# EK-TM4C129EXL_REV_A.net
KiCad netlist of a schematic drawn in EAGLE
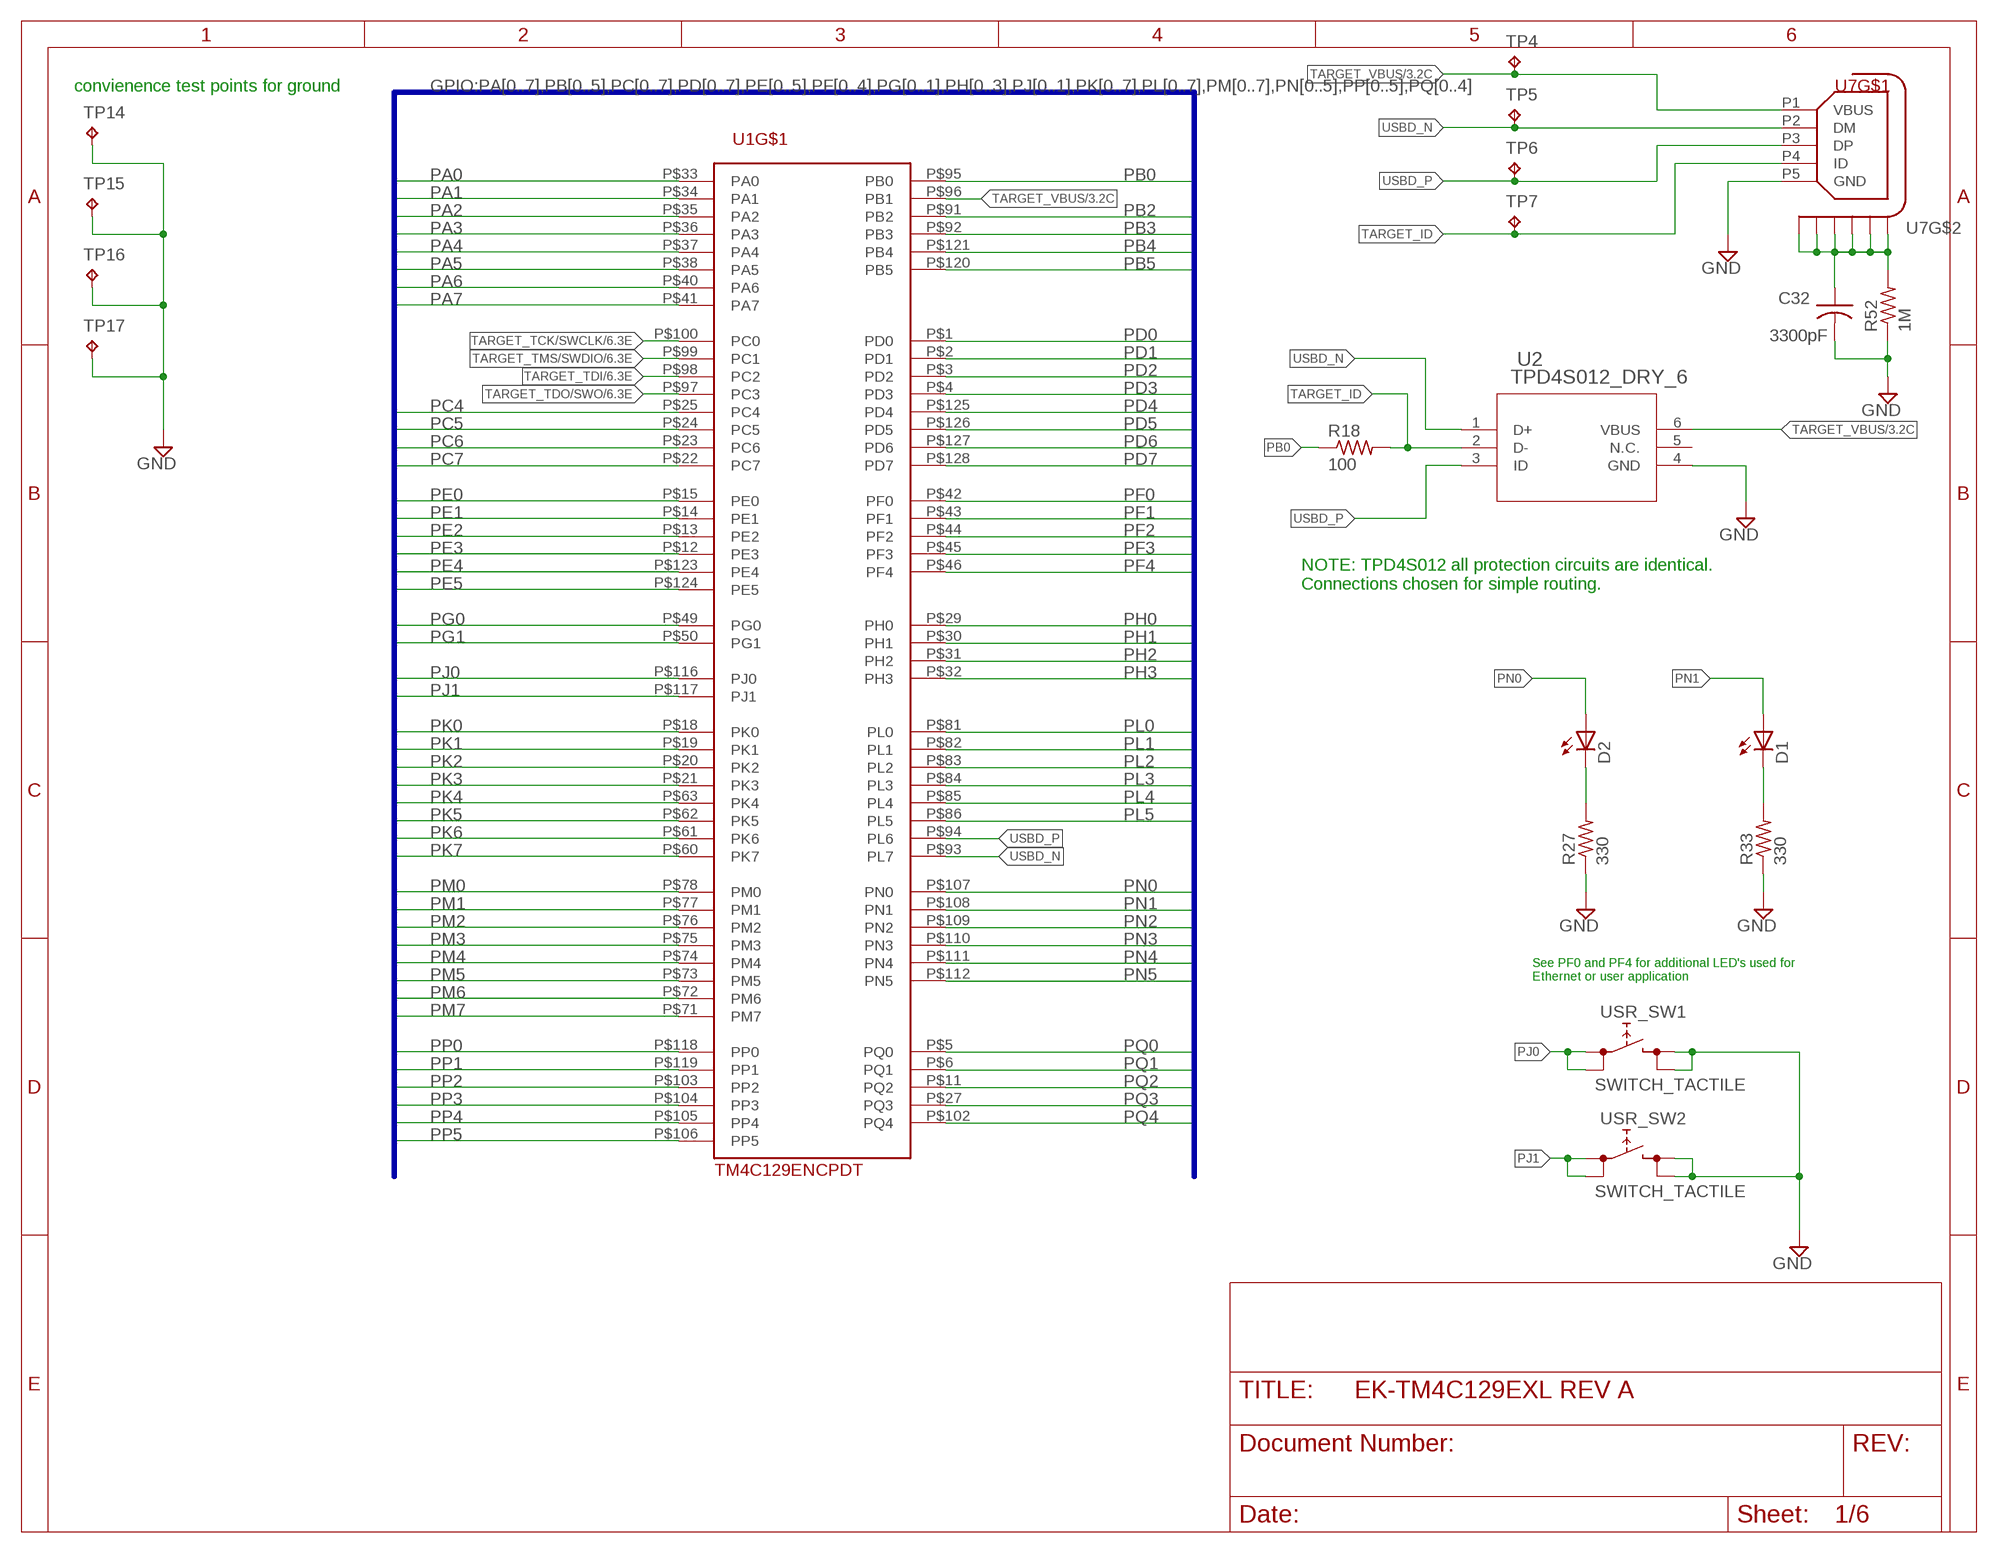
[diagram p0: schematic, sheet 1]
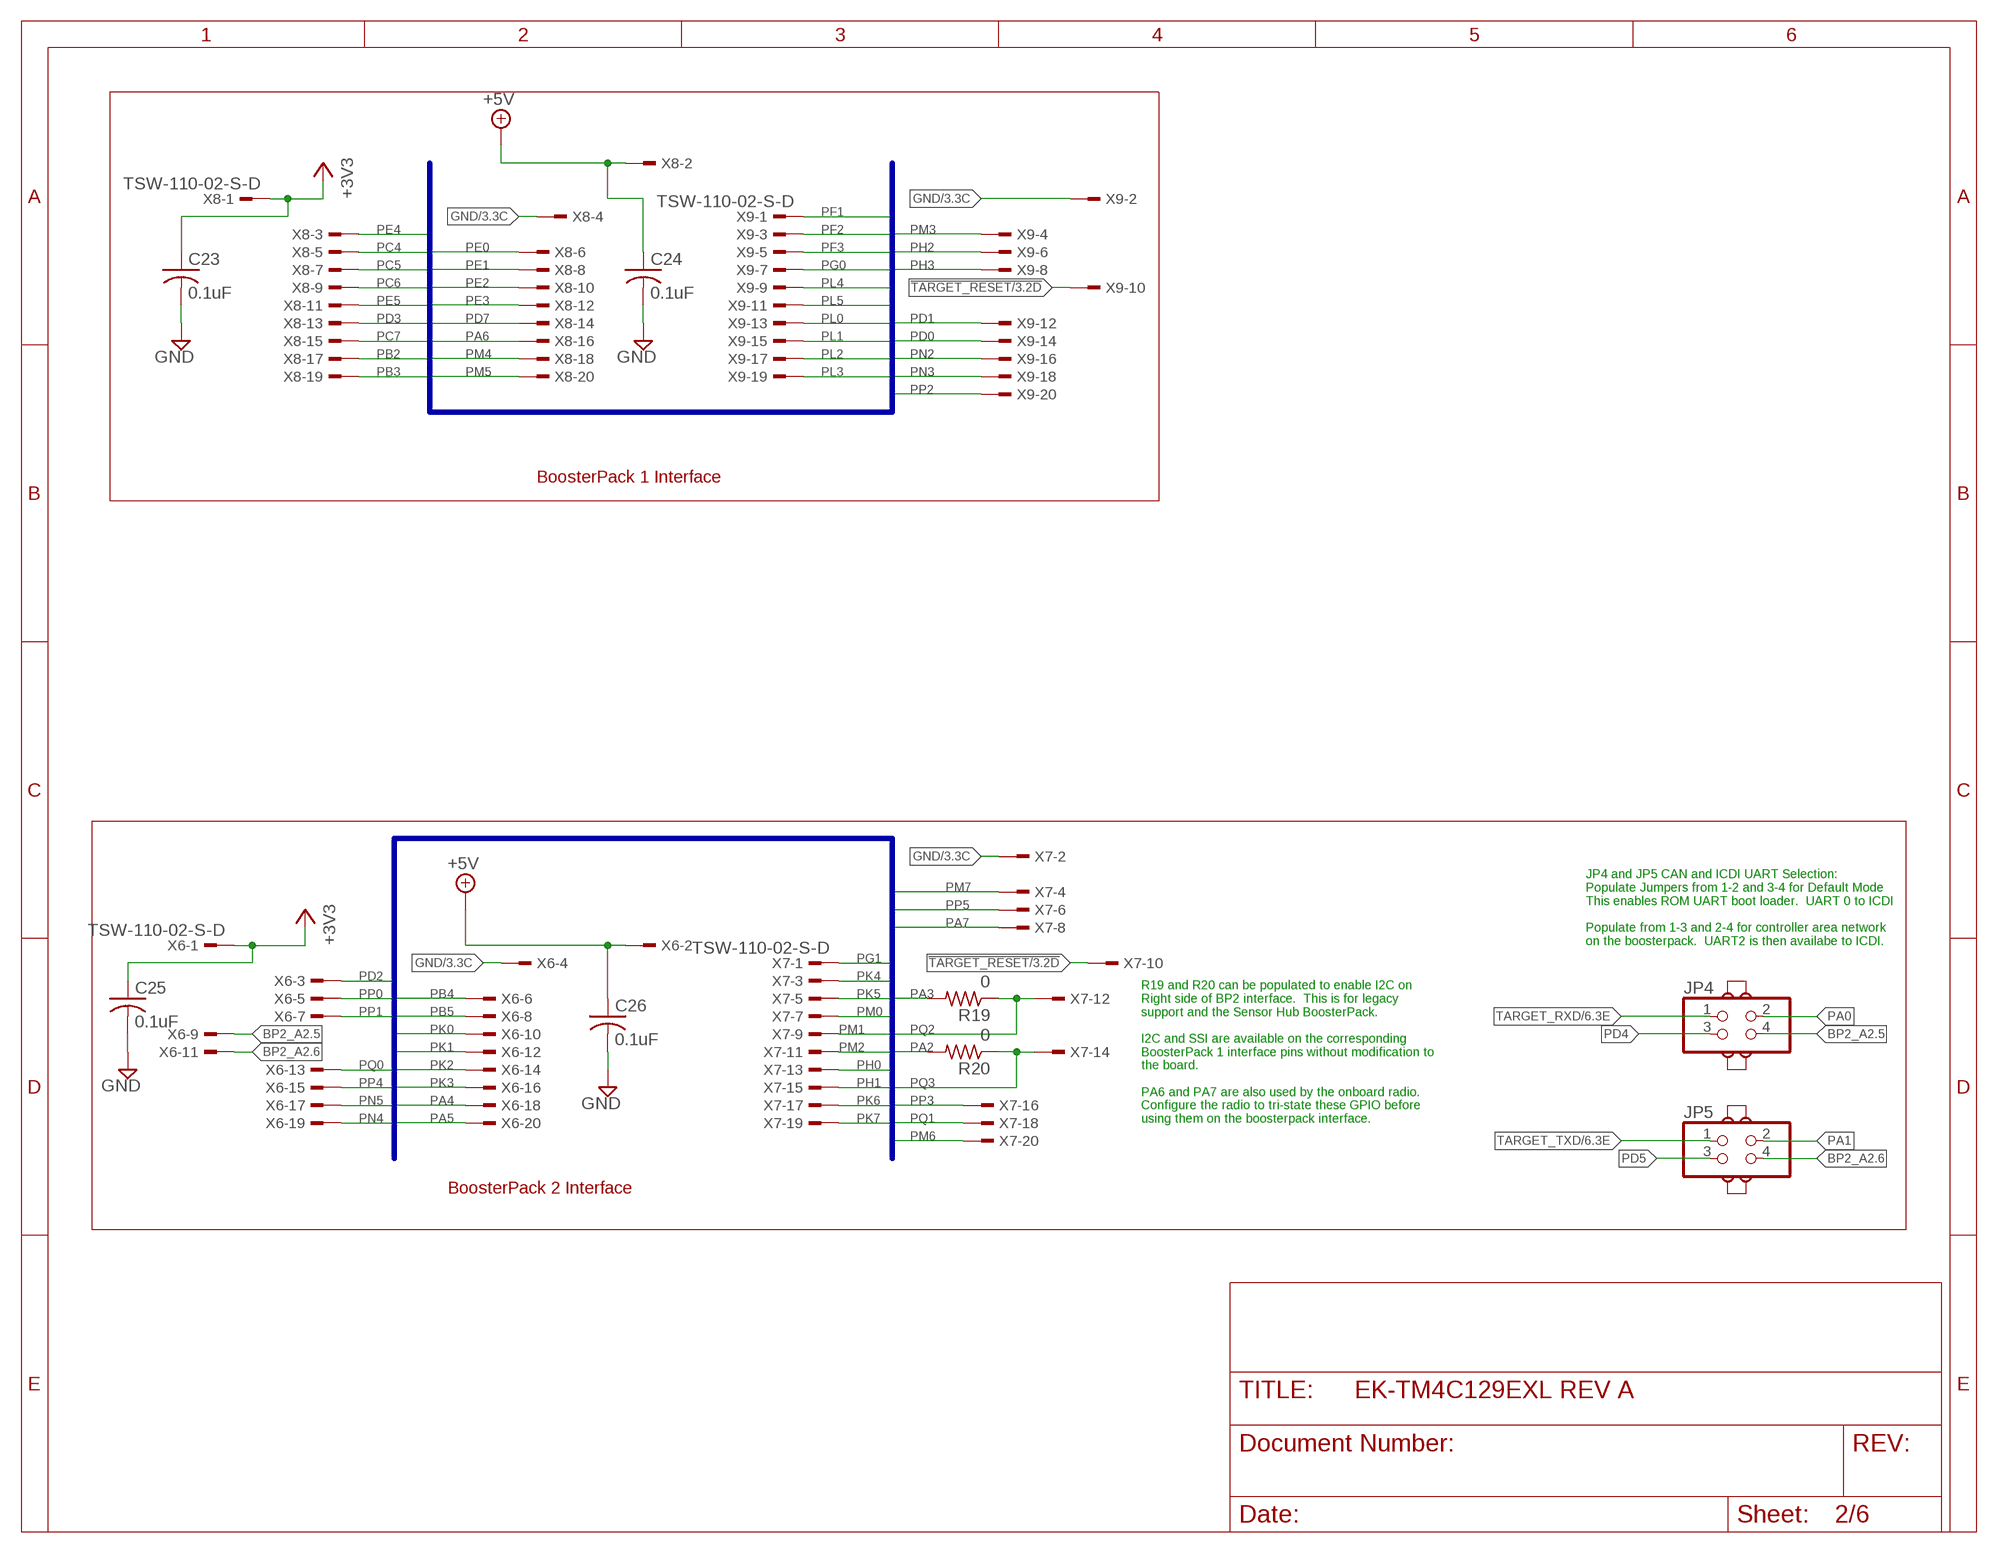
[diagram p1: schematic, sheet 2]
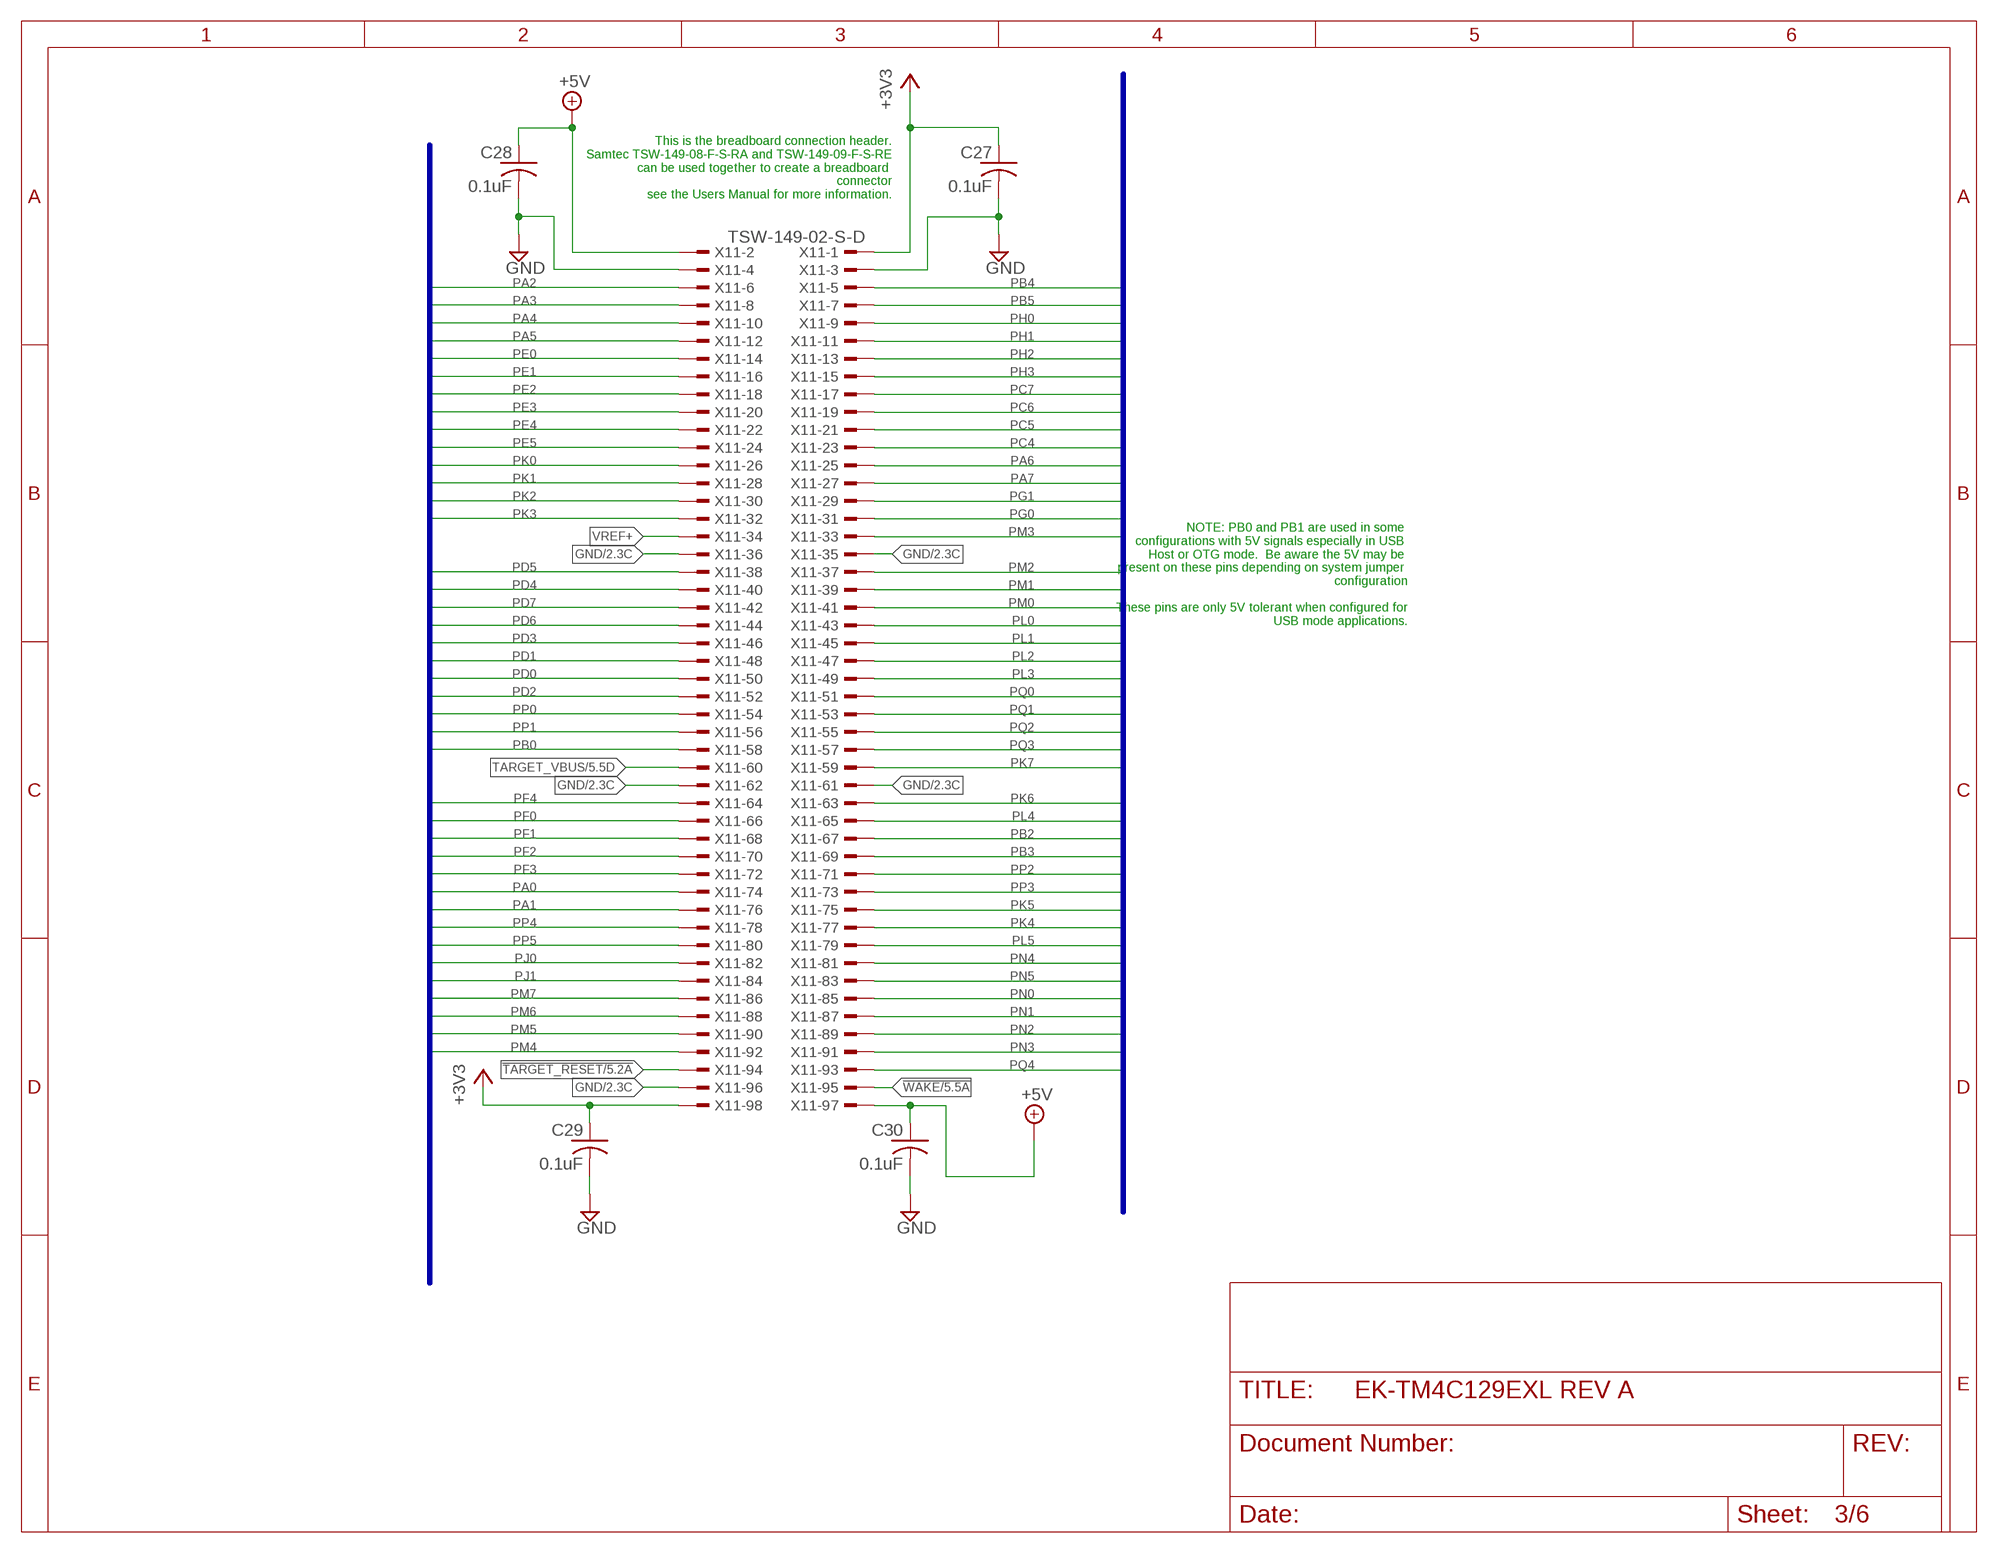
[diagram p2: schematic, sheet 3]
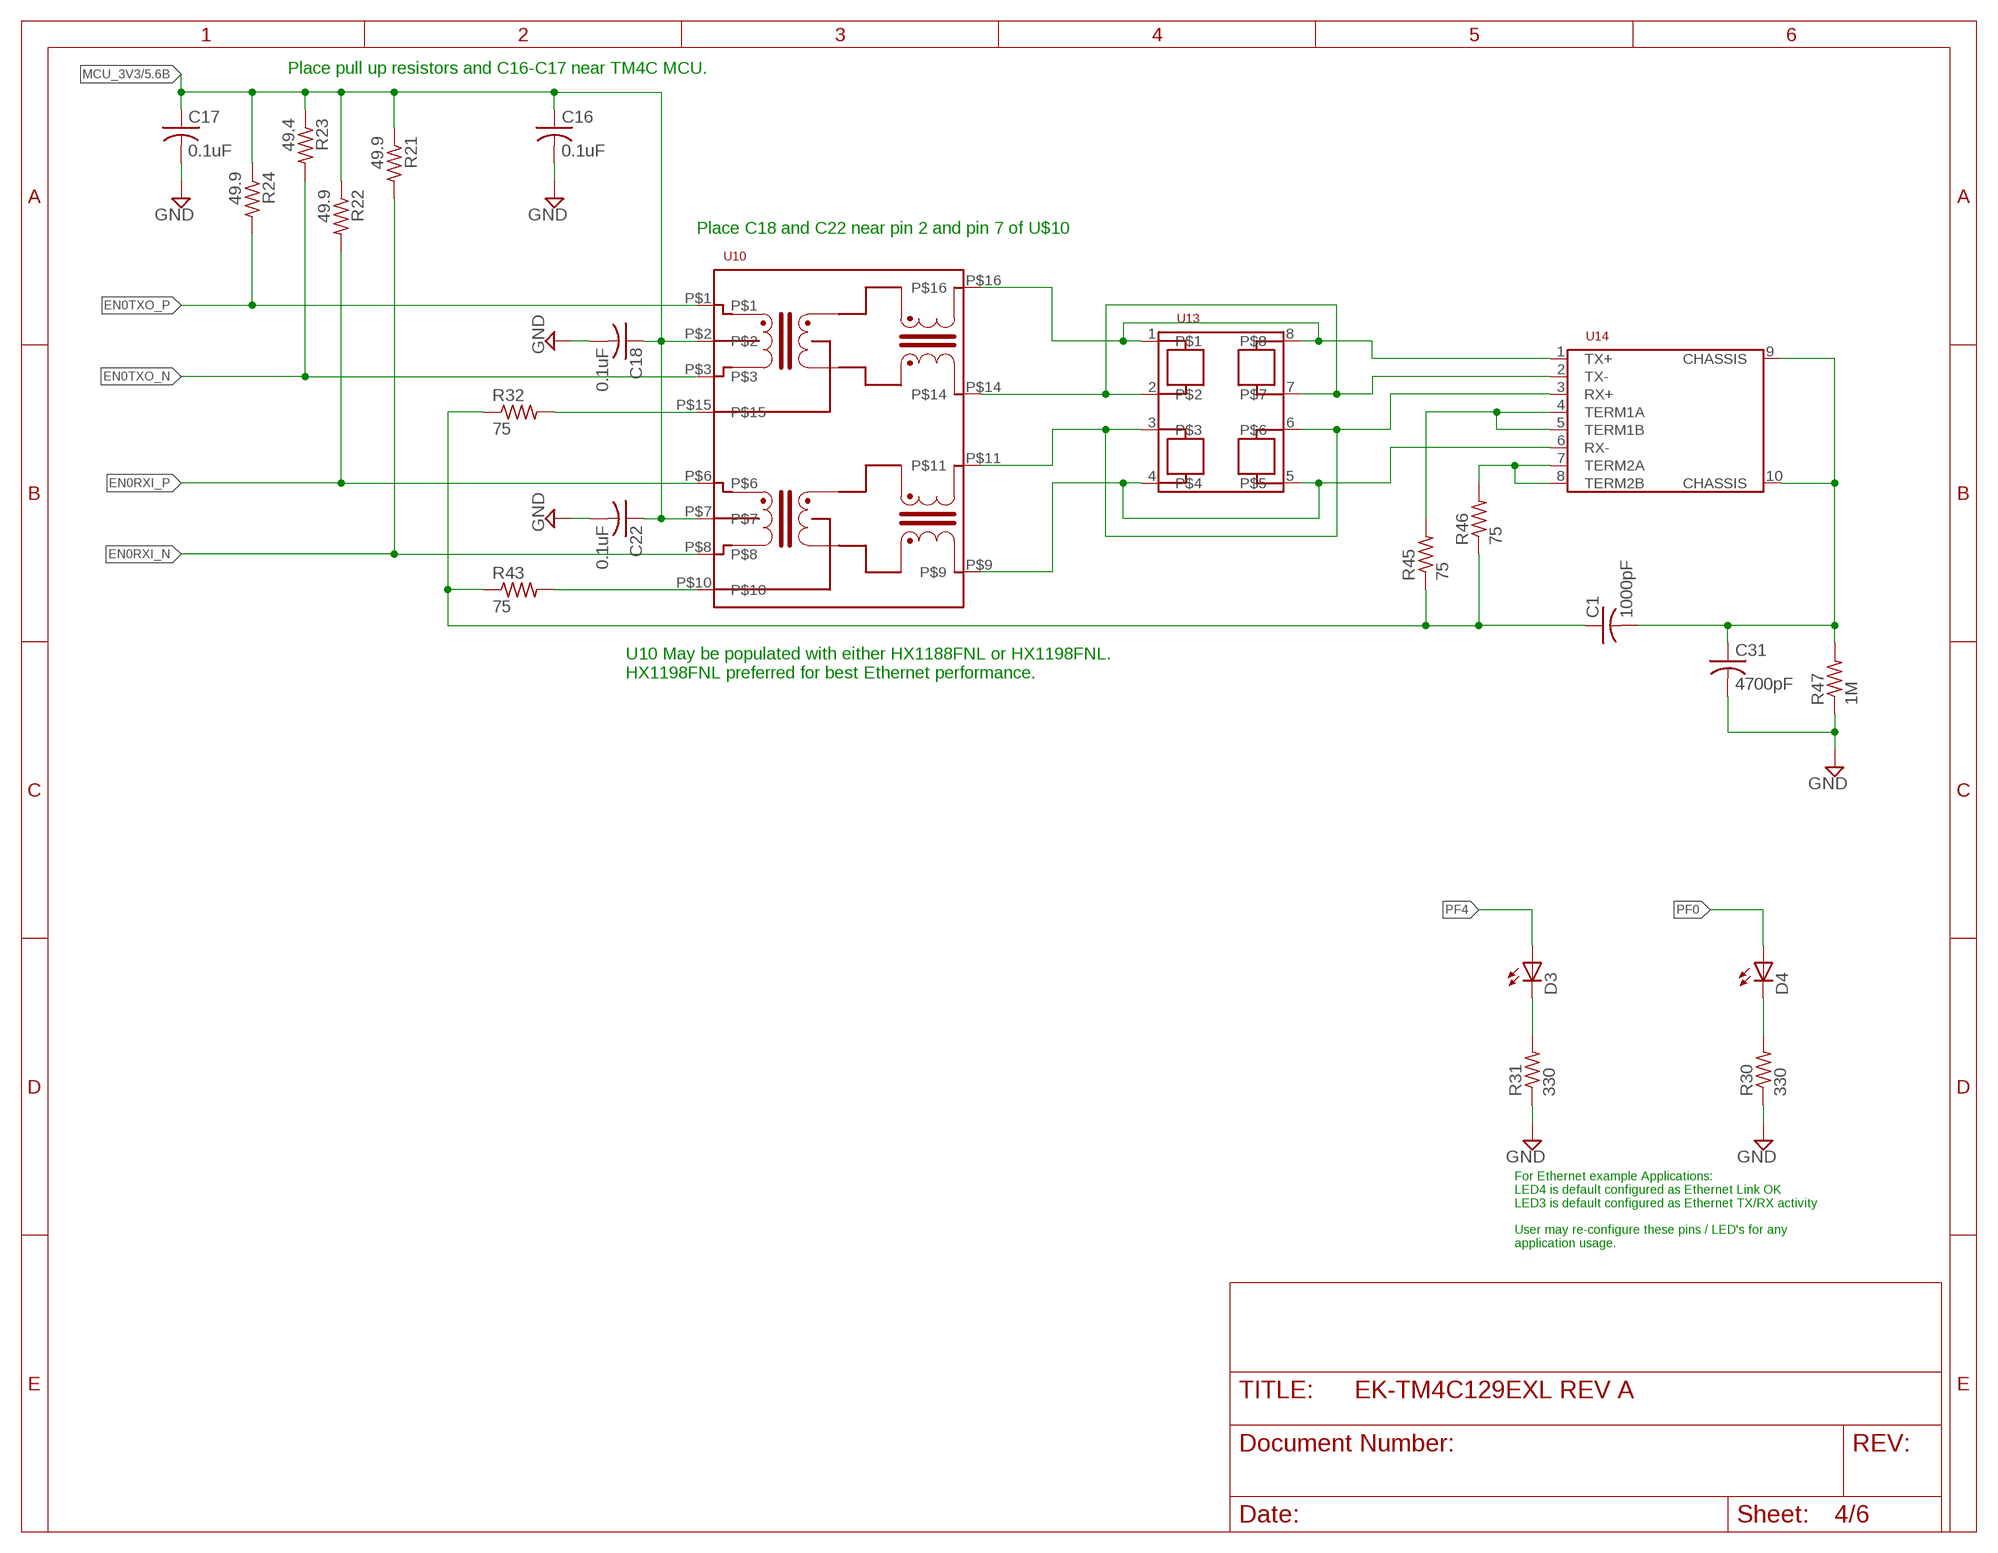
[diagram p3: schematic, sheet 4]
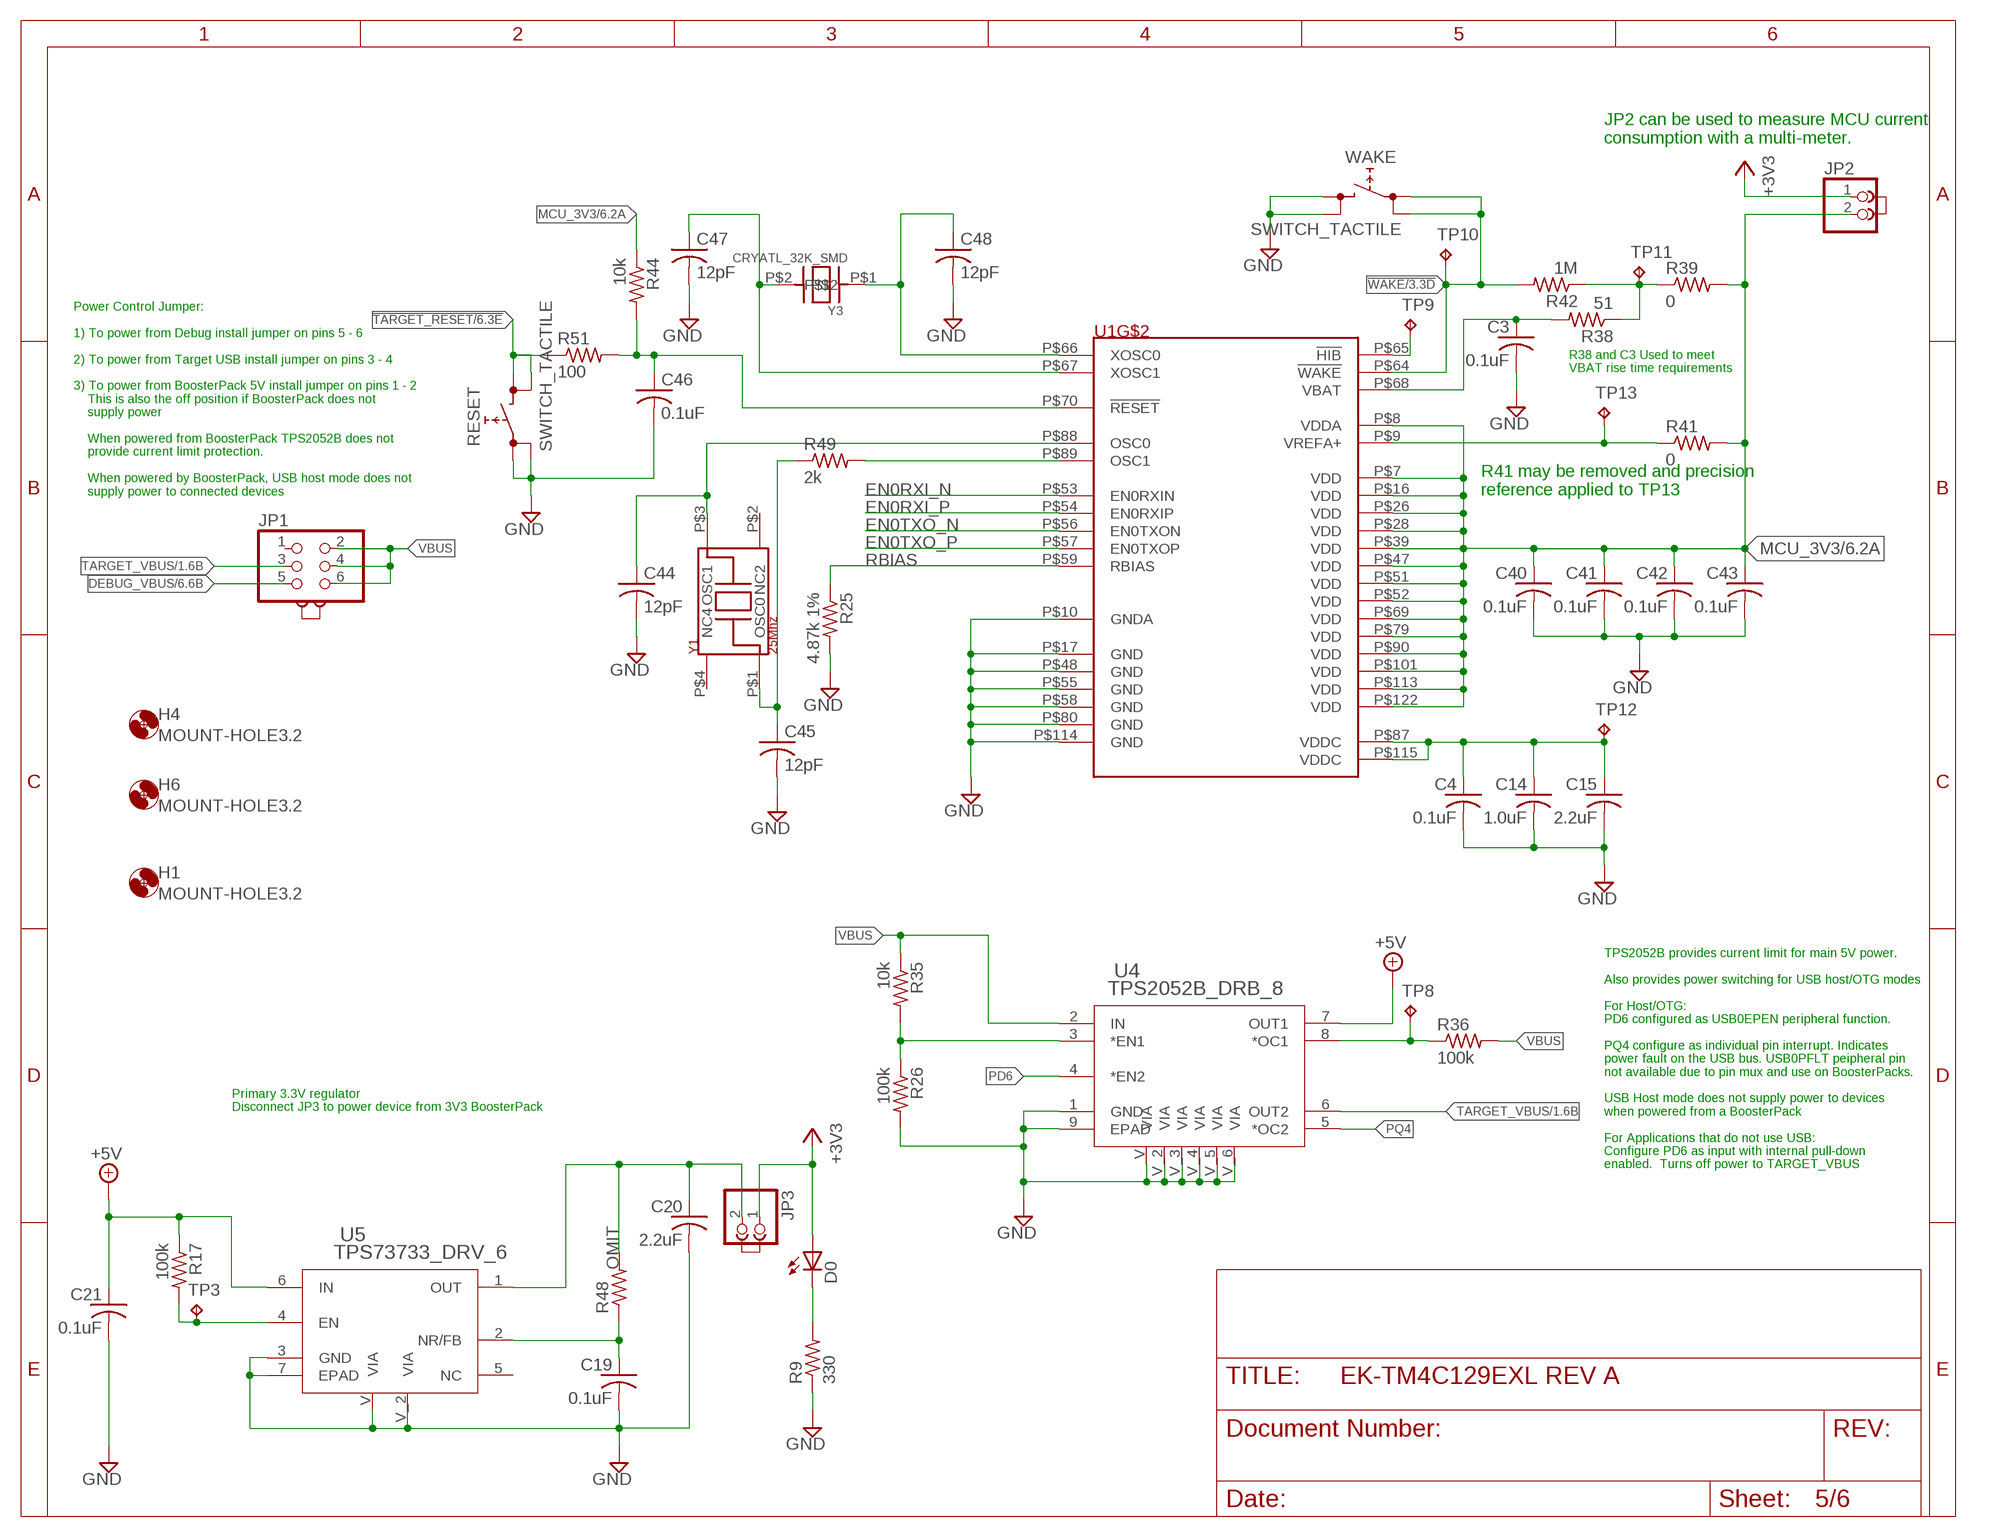
[diagram p4: schematic, sheet 5]
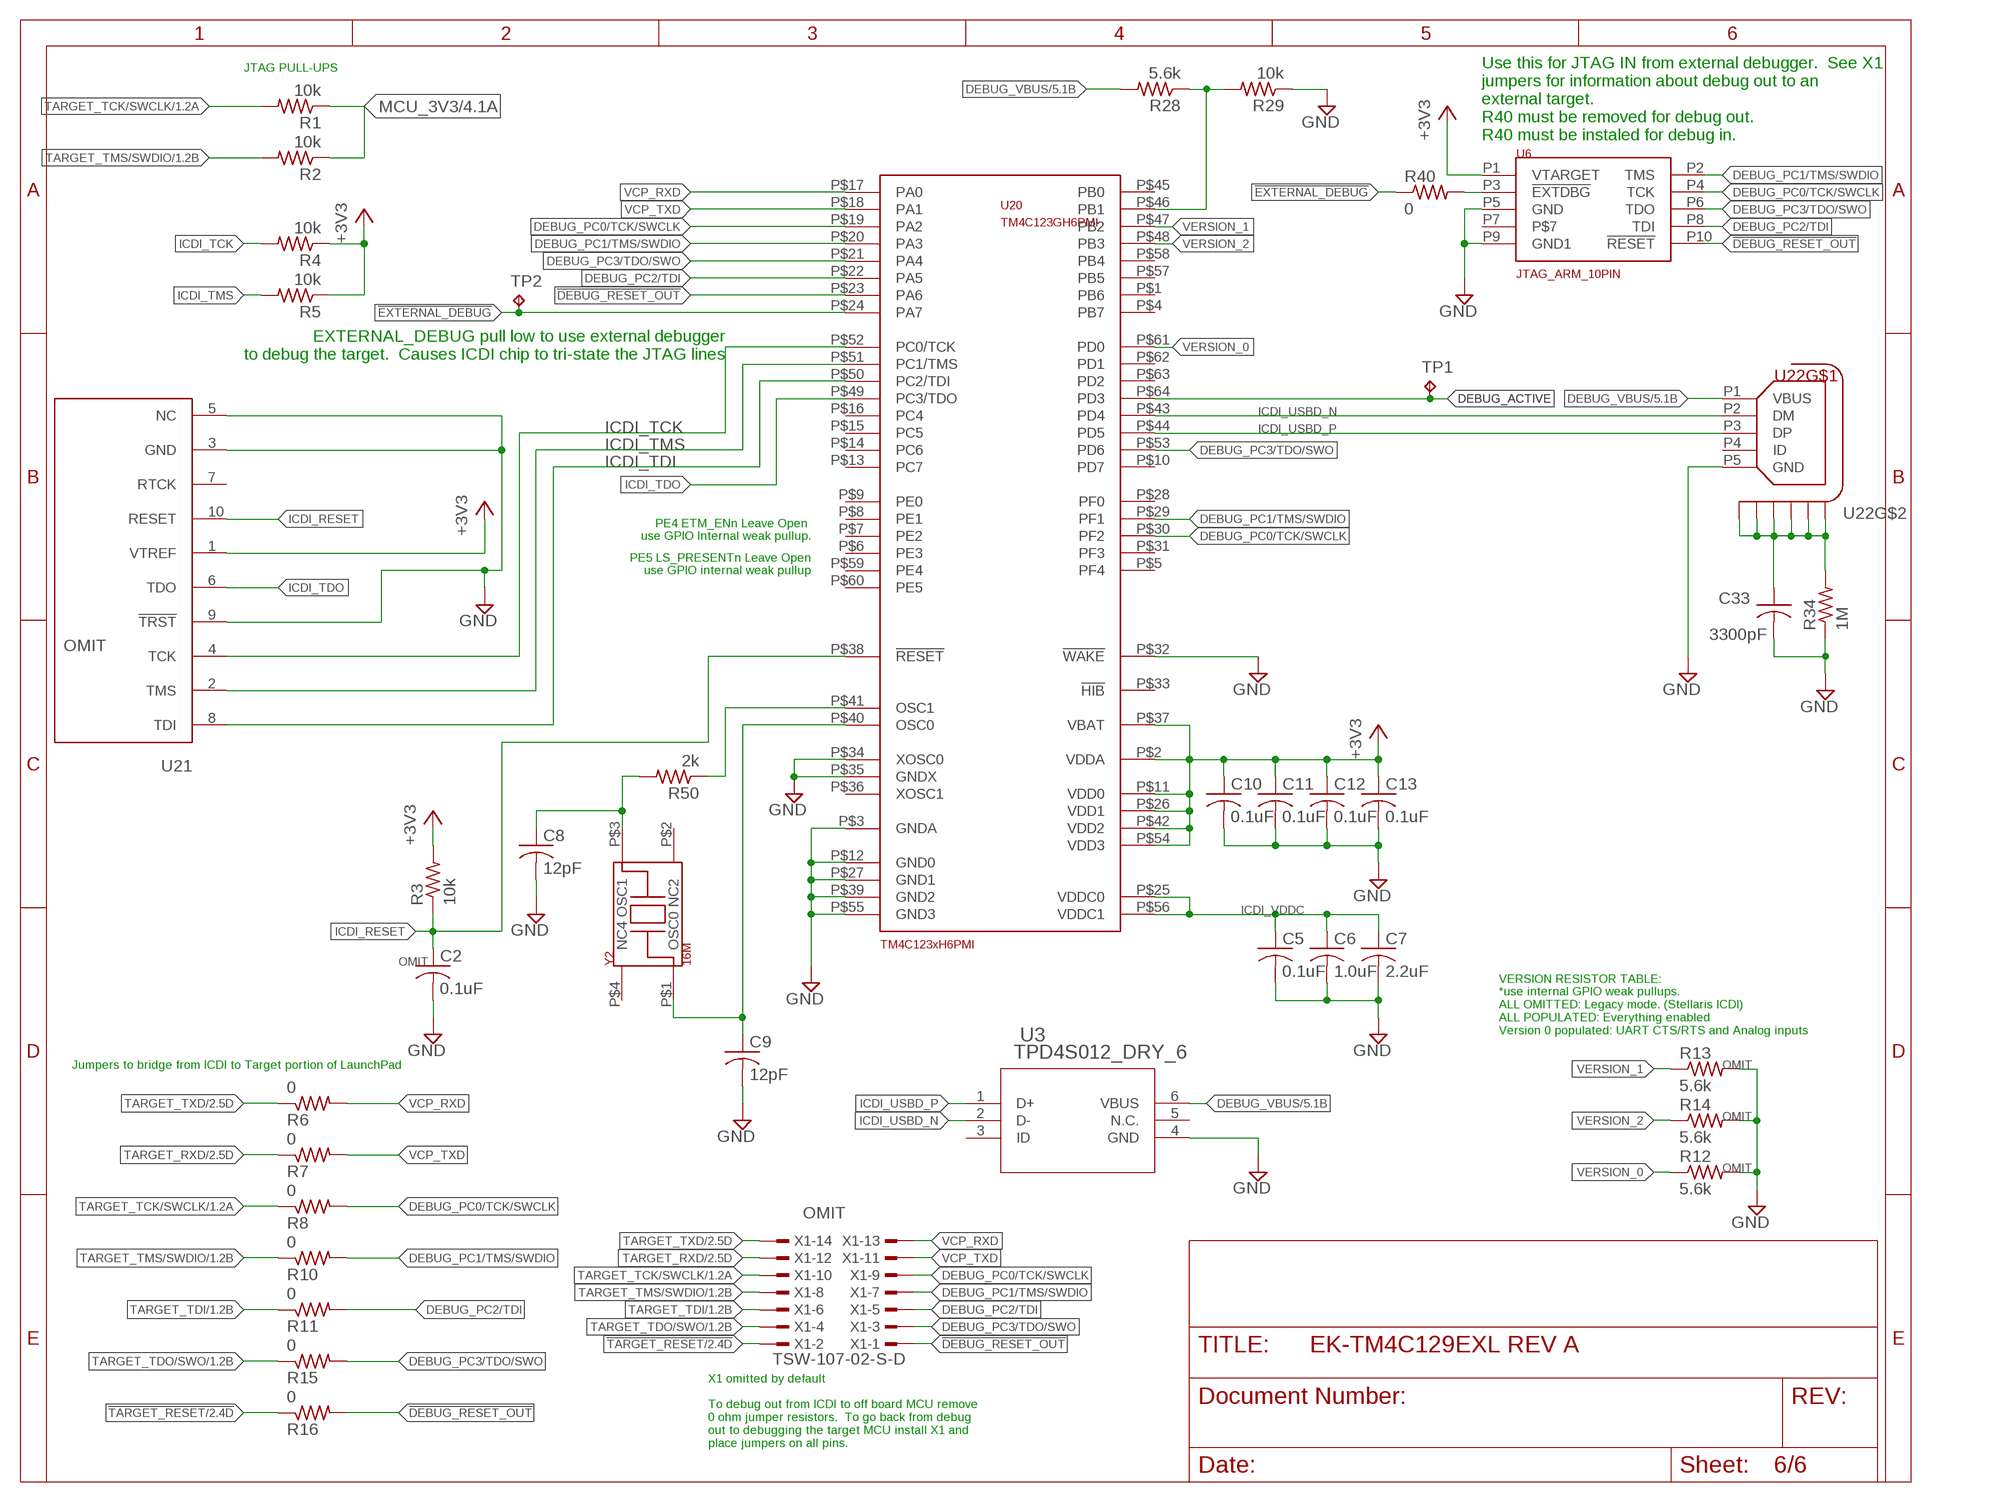
[diagram p5: schematic, sheet 6]

(export (version "E")
  (design (tool "Eeschema 10.0.6"))
  (components
    (comp (ref "C23")
      (value "0.1uF")
      (footprint "eagle-import:C0402")
      (libsource (lib "eagle-import") (part "ek-tm4c129exl_C-USC0402"))
    )
    (comp (ref "C24")
      (value "0.1uF")
      (footprint "eagle-import:C0402")
      (libsource (lib "eagle-import") (part "ek-tm4c129exl_C-USC0402"))
    )
    (comp (ref "C25")
      (value "0.1uF")
      (footprint "eagle-import:C0402")
      (libsource (lib "eagle-import") (part "ek-tm4c129exl_C-USC0402"))
    )
    (comp (ref "C26")
      (value "0.1uF")
      (footprint "eagle-import:C0402")
      (libsource (lib "eagle-import") (part "ek-tm4c129exl_C-USC0402"))
    )
    (comp (ref "J4")
      (value "JUMPER")
      (footprint "eagle-import:JUMP")
      (libsource (lib "eagle-import") (part "JUMPER"))
    )
    (comp (ref "J5")
      (value "JUMPER")
      (footprint "eagle-import:JUMP")
      (libsource (lib "eagle-import") (part "JUMPER"))
    )
    (comp (ref "J6")
      (value "JUMPER")
      (footprint "eagle-import:JUMP")
      (libsource (lib "eagle-import") (part "JUMPER"))
    )
    (comp (ref "J7")
      (value "JUMPER")
      (footprint "eagle-import:JUMP")
      (libsource (lib "eagle-import") (part "JUMPER"))
    )
    (comp (ref "JP4")
      (value "PINHD-2X2")
      (footprint "eagle-import:2X02")
      (libsource (lib "eagle-import") (part "PINHD-2X2"))
    )
    (comp (ref "JP5")
      (value "PINHD-2X2")
      (footprint "eagle-import:2X02")
      (libsource (lib "eagle-import") (part "PINHD-2X2"))
    )
    (comp (ref "R19")
      (value "0")
      (footprint "eagle-import:R0402")
      (libsource (lib "eagle-import") (part "ek-tm4c129exl_R-US_R0402"))
    )
    (comp (ref "R20")
      (value "0")
      (footprint "eagle-import:R0402")
      (libsource (lib "eagle-import") (part "ek-tm4c129exl_R-US_R0402"))
    )
    (comp (ref "X6")
      (value "TSW-110-02-S-D")
      (footprint "eagle-import:TSW-110-02-S-D")
      (fields (field (name "GNUM") "G22-THSTK-2X10-BAC"))
      (libsource (lib "eagle-import") (part "TSW-110-02-S-D"))
    )
    (comp (ref "X7")
      (value "TSW-110-02-S-D")
      (footprint "eagle-import:TSW-110-02-S-D")
      (fields (field (name "GNUM") "G22-THSTK-2X10-BAC"))
      (libsource (lib "eagle-import") (part "TSW-110-02-S-D"))
    )
    (comp (ref "X8")
      (value "TSW-110-02-S-D")
      (footprint "eagle-import:TSW-110-02-S-D")
      (fields (field (name "GNUM") "G22-THSTK-2X10-BAC"))
      (libsource (lib "eagle-import") (part "TSW-110-02-S-D"))
    )
    (comp (ref "X9")
      (value "TSW-110-02-S-D")
      (footprint "eagle-import:TSW-110-02-S-D")
      (fields (field (name "GNUM") "G22-THSTK-2X10-BAC"))
      (libsource (lib "eagle-import") (part "TSW-110-02-S-D"))
    )
    (comp (ref "C1")
      (value "1000pF")
      (footprint "eagle-import:C1210")
      (libsource (lib "eagle-import") (part "C-USC1210"))
    )
    (comp (ref "C16")
      (value "0.1uF")
      (footprint "eagle-import:C0402")
      (libsource (lib "eagle-import") (part "ek-tm4c129exl_C-USC0402"))
    )
    (comp (ref "C17")
      (value "0.1uF")
      (footprint "eagle-import:C0402")
      (libsource (lib "eagle-import") (part "ek-tm4c129exl_C-USC0402"))
    )
    (comp (ref "C18")
      (value "0.1uF")
      (footprint "eagle-import:C0402")
      (libsource (lib "eagle-import") (part "ek-tm4c129exl_C-USC0402"))
    )
    (comp (ref "C22")
      (value "0.1uF")
      (footprint "eagle-import:C0402")
      (libsource (lib "eagle-import") (part "ek-tm4c129exl_C-USC0402"))
    )
    (comp (ref "C31")
      (value "4700pF")
      (footprint "eagle-import:C1812")
      (libsource (lib "eagle-import") (part "ek-tm4c129exl_C-USC1812"))
    )
    (comp (ref "D3")
      (value "LEDCHIPLED_0603")
      (footprint "eagle-import:CHIPLED_0603")
      (libsource (lib "eagle-import") (part "LEDCHIPLED_0603"))
    )
    (comp (ref "D4")
      (value "LEDCHIPLED_0603")
      (footprint "eagle-import:CHIPLED_0603")
      (libsource (lib "eagle-import") (part "LEDCHIPLED_0603"))
    )
    (comp (ref "R21")
      (value "49.9")
      (footprint "eagle-import:R0402")
      (libsource (lib "eagle-import") (part "ek-tm4c129exl_R-US_R0402"))
    )
    (comp (ref "R22")
      (value "49.9")
      (footprint "eagle-import:R0402")
      (libsource (lib "eagle-import") (part "ek-tm4c129exl_R-US_R0402"))
    )
    (comp (ref "R23")
      (value "49.4")
      (footprint "eagle-import:R0402")
      (libsource (lib "eagle-import") (part "ek-tm4c129exl_R-US_R0402"))
    )
    (comp (ref "R24")
      (value "49.9")
      (footprint "eagle-import:R0402")
      (libsource (lib "eagle-import") (part "ek-tm4c129exl_R-US_R0402"))
    )
    (comp (ref "R30")
      (value "330")
      (footprint "eagle-import:R0402")
      (libsource (lib "eagle-import") (part "ek-tm4c129exl_R-US_R0402"))
    )
    (comp (ref "R31")
      (value "330")
      (footprint "eagle-import:R0402")
      (libsource (lib "eagle-import") (part "ek-tm4c129exl_R-US_R0402"))
    )
    (comp (ref "R32")
      (value "75")
      (footprint "eagle-import:R0402")
      (libsource (lib "eagle-import") (part "ek-tm4c129exl_R-US_R0402"))
    )
    (comp (ref "R43")
      (value "75")
      (footprint "eagle-import:R0402")
      (libsource (lib "eagle-import") (part "ek-tm4c129exl_R-US_R0402"))
    )
    (comp (ref "R45")
      (value "75")
      (footprint "eagle-import:R0402")
      (libsource (lib "eagle-import") (part "ek-tm4c129exl_R-US_R0402"))
    )
    (comp (ref "R46")
      (value "75")
      (footprint "eagle-import:R0402")
      (libsource (lib "eagle-import") (part "ek-tm4c129exl_R-US_R0402"))
    )
    (comp (ref "R47")
      (value "1M")
      (footprint "eagle-import:R1206")
      (libsource (lib "eagle-import") (part "R-US_R1206"))
    )
    (comp (ref "U10")
      (value "MAG_PULSE_HX1188FNL")
      (footprint "eagle-import:MAG_PULSE_HX1188FNL")
      (libsource (lib "eagle-import") (part "MAG_PULSE_HX1188FNL"))
    )
    (comp (ref "U13")
      (value "SLVU2.8-4")
      (footprint "eagle-import:D8")
      (libsource (lib "eagle-import") (part "SLVU2.8-4"))
    )
    (comp (ref "U14")
      (value "JACK_RJ45_NOMAG_NOLED_TECON")
      (footprint "eagle-import:RJ45_TE_CON_NOMAG_NOLED")
      (libsource (lib "eagle-import") (part "JACK_RJ45_NOMAG_NOLED_TECON"))
    )
    (comp (ref "C2")
      (value "0.1uF")
      (footprint "eagle-import:C0402")
      (fields (field (name "POPOP") "OMIT"))
      (libsource (lib "eagle-import") (part "ek-tm4c129exl_C-USC0402"))
    )
    (comp (ref "C5")
      (value "0.1uF")
      (footprint "eagle-import:C0402")
      (libsource (lib "eagle-import") (part "ek-tm4c129exl_C-USC0402"))
    )
    (comp (ref "C6")
      (value "1.0uF")
      (footprint "eagle-import:C0402")
      (libsource (lib "eagle-import") (part "ek-tm4c129exl_C-USC0402"))
    )
    (comp (ref "C7")
      (value "2.2uF")
      (footprint "eagle-import:C0603")
      (libsource (lib "eagle-import") (part "ek-tm4c129exl_C-USC0603"))
    )
    (comp (ref "C8")
      (value "12pF")
      (footprint "eagle-import:C0402")
      (libsource (lib "eagle-import") (part "ek-tm4c129exl_C-USC0402"))
    )
    (comp (ref "C9")
      (value "12pF")
      (footprint "eagle-import:C0402")
      (libsource (lib "eagle-import") (part "ek-tm4c129exl_C-USC0402"))
    )
    (comp (ref "C10")
      (value "0.1uF")
      (footprint "eagle-import:C0402")
      (libsource (lib "eagle-import") (part "ek-tm4c129exl_C-USC0402"))
    )
    (comp (ref "C11")
      (value "0.1uF")
      (footprint "eagle-import:C0402")
      (libsource (lib "eagle-import") (part "ek-tm4c129exl_C-USC0402"))
    )
    (comp (ref "C12")
      (value "0.1uF")
      (footprint "eagle-import:C0402")
      (libsource (lib "eagle-import") (part "ek-tm4c129exl_C-USC0402"))
    )
    (comp (ref "C13")
      (value "0.1uF")
      (footprint "eagle-import:C0402")
      (libsource (lib "eagle-import") (part "ek-tm4c129exl_C-USC0402"))
    )
    (comp (ref "C33")
      (value "3300pF")
      (footprint "eagle-import:C0603")
      (libsource (lib "eagle-import") (part "C-USC0603"))
    )
    (comp (ref "R1")
      (value "10k")
      (footprint "eagle-import:R0402")
      (libsource (lib "eagle-import") (part "ek-tm4c129exl_R-US_R0402"))
    )
    (comp (ref "R2")
      (value "10k")
      (footprint "eagle-import:R0402")
      (libsource (lib "eagle-import") (part "ek-tm4c129exl_R-US_R0402"))
    )
    (comp (ref "R3")
      (value "10k")
      (footprint "eagle-import:R0402")
      (libsource (lib "eagle-import") (part "ek-tm4c129exl_R-US_R0402"))
    )
    (comp (ref "R4")
      (value "10k")
      (footprint "eagle-import:R0402")
      (libsource (lib "eagle-import") (part "ek-tm4c129exl_R-US_R0402"))
    )
    (comp (ref "R5")
      (value "10k")
      (footprint "eagle-import:R0402")
      (libsource (lib "eagle-import") (part "ek-tm4c129exl_R-US_R0402"))
    )
    (comp (ref "R6")
      (value "0")
      (footprint "eagle-import:R0402")
      (libsource (lib "eagle-import") (part "ek-tm4c129exl_R-US_R0402"))
    )
    (comp (ref "R7")
      (value "0")
      (footprint "eagle-import:R0402")
      (libsource (lib "eagle-import") (part "ek-tm4c129exl_R-US_R0402"))
    )
    (comp (ref "R8")
      (value "0")
      (footprint "eagle-import:R0402")
      (libsource (lib "eagle-import") (part "ek-tm4c129exl_R-US_R0402"))
    )
    (comp (ref "R10")
      (value "0")
      (footprint "eagle-import:R0402")
      (libsource (lib "eagle-import") (part "ek-tm4c129exl_R-US_R0402"))
    )
    (comp (ref "R11")
      (value "0")
      (footprint "eagle-import:R0402")
      (libsource (lib "eagle-import") (part "ek-tm4c129exl_R-US_R0402"))
    )
    (comp (ref "R12")
      (value "5.6k")
      (footprint "eagle-import:R0402")
      (fields (field (name "POPOP") "OMIT"))
      (libsource (lib "eagle-import") (part "ek-tm4c129exl_R-US_R0402"))
    )
    (comp (ref "R13")
      (value "5.6k")
      (footprint "eagle-import:R0402")
      (fields (field (name "POPOP") "OMIT"))
      (libsource (lib "eagle-import") (part "ek-tm4c129exl_R-US_R0402"))
    )
    (comp (ref "R14")
      (value "5.6k")
      (footprint "eagle-import:R0402")
      (fields (field (name "POPOP") "OMIT"))
      (libsource (lib "eagle-import") (part "ek-tm4c129exl_R-US_R0402"))
    )
    (comp (ref "R15")
      (value "0")
      (footprint "eagle-import:R0402")
      (libsource (lib "eagle-import") (part "ek-tm4c129exl_R-US_R0402"))
    )
    (comp (ref "R16")
      (value "0")
      (footprint "eagle-import:R0402")
      (libsource (lib "eagle-import") (part "ek-tm4c129exl_R-US_R0402"))
    )
    (comp (ref "R28")
      (value "5.6k")
      (footprint "eagle-import:R0402")
      (libsource (lib "eagle-import") (part "ek-tm4c129exl_R-US_R0402"))
    )
    (comp (ref "R29")
      (value "10k")
      (footprint "eagle-import:R0402")
      (libsource (lib "eagle-import") (part "ek-tm4c129exl_R-US_R0402"))
    )
    (comp (ref "R34")
      (value "1M")
      (footprint "eagle-import:R0603")
      (libsource (lib "eagle-import") (part "R-US_R0603"))
    )
    (comp (ref "R40")
      (value "0")
      (footprint "eagle-import:R0402")
      (libsource (lib "eagle-import") (part "ek-tm4c129exl_R-US_R0402"))
    )
    (comp (ref "R50")
      (value "2k")
      (footprint "eagle-import:R0402")
      (libsource (lib "eagle-import") (part "ek-tm4c129exl_R-US_R0402"))
    )
    (comp (ref "TP1")
      (value "TPPAD1-13")
      (footprint "eagle-import:P1-13")
      (libsource (lib "eagle-import") (part "TPPAD1-13"))
    )
    (comp (ref "TP2")
      (value "TPPAD1-13")
      (footprint "eagle-import:P1-13")
      (libsource (lib "eagle-import") (part "TPPAD1-13"))
    )
    (comp (ref "U3")
      (value "TPD4S012_DRY_6")
      (footprint "eagle-import:DRY6")
      (fields
        (field (name "GENERIC_PART_NUMBER") "TPD4S012")
        (field (name "MANUFACTURER") "Texas Instruments")
        (field (name "MANUFACTURER_PART_NUMBER") "tpd4s012_dry_6")
      )
      (libsource (lib "eagle-import") (part "TPD4S012_DRY_6"))
    )
    (comp (ref "U6")
      (value "JTAG_ARM_10PIN")
      (footprint "eagle-import:CON_2X5_50MIL")
      (libsource (lib "eagle-import") (part "JTAG_ARM_10PIN"))
    )
    (comp (ref "U20")
      (value "TM4C123GH6PMI")
      (footprint "eagle-import:LQFP-64-PM")
      (libsource (lib "eagle-import") (part "TM4C123GH6PMI"))
    )
    (comp (ref "U21")
      (value "TC2050-NL-MCP-NL")
      (footprint "eagle-import:TC2030-MCP-NL")
      (fields (field (name "POPOP") "OMIT"))
      (libsource (lib "eagle-import") (part "TC2050-NL-MCP-NL"))
    )
    (comp (ref "U22")
      (value "CON_USB_FCI_MICRO_B_10118194")
      (footprint "eagle-import:CON_USB_MICRO_B_FCI_10118194")
      (fields (field (name "GNUM") "G20-USBU-THB-CEB"))
      (libsource (lib "eagle-import") (part "CON_USB_FCI_MICRO_B_10118194"))
    )
    (comp (ref "X1")
      (value "TSW-107-02-S-D")
      (footprint "eagle-import:TSW-107-02-S-D")
      (fields (field (name "GNUM") "G22-THVEU-2X7P-BAB") (field (name "POPOP") "OMIT"))
      (libsource (lib "eagle-import") (part "TSW-107-02-S-D"))
    )
    (comp (ref "Y2")
      (value "16M")
      (footprint "eagle-import:NDK3.2X2.5")
      (libsource (lib "eagle-import") (part "NX3225GA"))
    )
    (comp (ref "C3")
      (value "0.1uF")
      (footprint "eagle-import:C0402")
      (libsource (lib "eagle-import") (part "ek-tm4c129exl_C-USC0402"))
    )
    (comp (ref "C4")
      (value "0.1uF")
      (footprint "eagle-import:C0402")
      (libsource (lib "eagle-import") (part "ek-tm4c129exl_C-USC0402"))
    )
    (comp (ref "C14")
      (value "1.0uF")
      (footprint "eagle-import:C0402")
      (libsource (lib "eagle-import") (part "ek-tm4c129exl_C-USC0402"))
    )
    (comp (ref "C15")
      (value "2.2uF")
      (footprint "eagle-import:C0603K")
      (fields (field (name "DIGIKEY_PARTNUM") "311-1451-2-ND"))
      (libsource (lib "eagle-import") (part "ek-tm4c129exl_C-USC0603K"))
    )
    (comp (ref "C19")
      (value "0.1uF")
      (footprint "eagle-import:C0402")
      (libsource (lib "eagle-import") (part "ek-tm4c129exl_C-USC0402"))
    )
    (comp (ref "C20")
      (value "2.2uF")
      (footprint "eagle-import:C0603K")
      (fields (field (name "DIGIKEY_PARTNUM") "311-1451-2-ND"))
      (libsource (lib "eagle-import") (part "ek-tm4c129exl_C-USC0603K"))
    )
    (comp (ref "C21")
      (value "0.1uF")
      (footprint "eagle-import:C0402")
      (libsource (lib "eagle-import") (part "ek-tm4c129exl_C-USC0402"))
    )
    (comp (ref "C40")
      (value "0.1uF")
      (footprint "eagle-import:C0402")
      (libsource (lib "eagle-import") (part "ek-tm4c129exl_C-USC0402"))
    )
    (comp (ref "C41")
      (value "0.1uF")
      (footprint "eagle-import:C0402")
      (libsource (lib "eagle-import") (part "ek-tm4c129exl_C-USC0402"))
    )
    (comp (ref "C42")
      (value "0.1uF")
      (footprint "eagle-import:C0402")
      (libsource (lib "eagle-import") (part "ek-tm4c129exl_C-USC0402"))
    )
    (comp (ref "C43")
      (value "0.1uF")
      (footprint "eagle-import:C0402")
      (libsource (lib "eagle-import") (part "ek-tm4c129exl_C-USC0402"))
    )
    (comp (ref "C44")
      (value "12pF")
      (footprint "eagle-import:C0402")
      (libsource (lib "eagle-import") (part "ek-tm4c129exl_C-USC0402"))
    )
    (comp (ref "C45")
      (value "12pF")
      (footprint "eagle-import:C0402")
      (libsource (lib "eagle-import") (part "ek-tm4c129exl_C-USC0402"))
    )
    (comp (ref "C46")
      (value "0.1uF")
      (footprint "eagle-import:C0402")
      (libsource (lib "eagle-import") (part "ek-tm4c129exl_C-USC0402"))
    )
    (comp (ref "C47")
      (value "12pF")
      (footprint "eagle-import:C0402")
      (libsource (lib "eagle-import") (part "ek-tm4c129exl_C-USC0402"))
    )
    (comp (ref "C48")
      (value "12pF")
      (footprint "eagle-import:C0402")
      (libsource (lib "eagle-import") (part "ek-tm4c129exl_C-USC0402"))
    )
    (comp (ref "D0")
      (value "LEDCHIPLED_0603")
      (footprint "eagle-import:CHIPLED_0603")
      (libsource (lib "eagle-import") (part "LEDCHIPLED_0603"))
    )
    (comp (ref "H1")
      (value "MOUNT-HOLE3.2")
      (footprint "eagle-import:3,2")
      (libsource (lib "eagle-import") (part "MOUNT-HOLE3.2"))
    )
    (comp (ref "H4")
      (value "MOUNT-HOLE3.2")
      (footprint "eagle-import:3,2")
      (libsource (lib "eagle-import") (part "MOUNT-HOLE3.2"))
    )
    (comp (ref "H6")
      (value "MOUNT-HOLE3.2")
      (footprint "eagle-import:3,2")
      (libsource (lib "eagle-import") (part "MOUNT-HOLE3.2"))
    )
    (comp (ref "J1")
      (value "JUMPER")
      (footprint "eagle-import:JUMP")
      (libsource (lib "eagle-import") (part "JUMPER"))
    )
    (comp (ref "J2")
      (value "JUMPER")
      (footprint "eagle-import:JUMP")
      (libsource (lib "eagle-import") (part "JUMPER"))
    )
    (comp (ref "J3")
      (value "JUMPER")
      (footprint "eagle-import:JUMP")
      (libsource (lib "eagle-import") (part "JUMPER"))
    )
    (comp (ref "JP1")
      (value "PINHD-2X3")
      (footprint "eagle-import:2X03")
      (libsource (lib "eagle-import") (part "PINHD-2X3"))
    )
    (comp (ref "JP2")
      (value "PINHD-1X2")
      (footprint "eagle-import:1X02")
      (libsource (lib "eagle-import") (part "PINHD-1X2"))
    )
    (comp (ref "JP3")
      (value "PINHD-1X2")
      (footprint "eagle-import:1X02")
      (libsource (lib "eagle-import") (part "PINHD-1X2"))
    )
    (comp (ref "R9")
      (value "330")
      (footprint "eagle-import:R0402")
      (libsource (lib "eagle-import") (part "ek-tm4c129exl_R-US_R0402"))
    )
    (comp (ref "R17")
      (value "100k")
      (footprint "eagle-import:R0402")
      (libsource (lib "eagle-import") (part "ek-tm4c129exl_R-US_R0402"))
    )
    (comp (ref "R25")
      (value "4.87k 1%")
      (footprint "eagle-import:R0402")
      (libsource (lib "eagle-import") (part "ek-tm4c129exl_R-US_R0402"))
    )
    (comp (ref "R26")
      (value "100k")
      (footprint "eagle-import:R0402")
      (libsource (lib "eagle-import") (part "ek-tm4c129exl_R-US_R0402"))
    )
    (comp (ref "R35")
      (value "10k")
      (footprint "eagle-import:R0402")
      (libsource (lib "eagle-import") (part "ek-tm4c129exl_R-US_R0402"))
    )
    (comp (ref "R36")
      (value "100k")
      (footprint "eagle-import:R0402")
      (libsource (lib "eagle-import") (part "ek-tm4c129exl_R-US_R0402"))
    )
    (comp (ref "R38")
      (value "51")
      (footprint "eagle-import:R0402")
      (libsource (lib "eagle-import") (part "ek-tm4c129exl_R-US_R0402"))
    )
    (comp (ref "R39")
      (value "0")
      (footprint "eagle-import:R0402")
      (libsource (lib "eagle-import") (part "ek-tm4c129exl_R-US_R0402"))
    )
    (comp (ref "R41")
      (value "0")
      (footprint "eagle-import:R0402")
      (libsource (lib "eagle-import") (part "ek-tm4c129exl_R-US_R0402"))
    )
    (comp (ref "R42")
      (value "1M")
      (footprint "eagle-import:R0402")
      (libsource (lib "eagle-import") (part "ek-tm4c129exl_R-US_R0402"))
    )
    (comp (ref "R44")
      (value "10k")
      (footprint "eagle-import:R0402")
      (libsource (lib "eagle-import") (part "ek-tm4c129exl_R-US_R0402"))
    )
    (comp (ref "R48")
      (value "R-US_R0402")
      (footprint "eagle-import:R0402")
      (fields (field (name "POPOP") "OMIT"))
      (libsource (lib "eagle-import") (part "ek-tm4c129exl_R-US_R0402"))
    )
    (comp (ref "R49")
      (value "2k")
      (footprint "eagle-import:R0402")
      (libsource (lib "eagle-import") (part "ek-tm4c129exl_R-US_R0402"))
    )
    (comp (ref "R51")
      (value "100")
      (footprint "eagle-import:R0402")
      (libsource (lib "eagle-import") (part "ek-tm4c129exl_R-US_R0402"))
    )
    (comp (ref "RESET")
      (value "SWITCH_TACTILE")
      (footprint "eagle-import:SWITCH_6MM_6MM_TE_CON_SMD")
      (libsource (lib "eagle-import") (part "SWITCH_TACTILE"))
    )
    (comp (ref "TP3")
      (value "TPPAD1-13")
      (footprint "eagle-import:P1-13")
      (libsource (lib "eagle-import") (part "TPPAD1-13"))
    )
    (comp (ref "TP8")
      (value "TPPAD1-13")
      (footprint "eagle-import:P1-13")
      (libsource (lib "eagle-import") (part "TPPAD1-13"))
    )
    (comp (ref "TP9")
      (value "TPPAD1-13")
      (footprint "eagle-import:P1-13")
      (libsource (lib "eagle-import") (part "TPPAD1-13"))
    )
    (comp (ref "TP10")
      (value "TPPAD1-13")
      (footprint "eagle-import:P1-13")
      (libsource (lib "eagle-import") (part "TPPAD1-13"))
    )
    (comp (ref "TP11")
      (value "TPPAD1-13")
      (footprint "eagle-import:P1-13")
      (libsource (lib "eagle-import") (part "TPPAD1-13"))
    )
    (comp (ref "TP12")
      (value "TPPAD1-13")
      (footprint "eagle-import:P1-13")
      (libsource (lib "eagle-import") (part "TPPAD1-13"))
    )
    (comp (ref "TP13")
      (value "TPPAD1-13")
      (footprint "eagle-import:P1-13")
      (libsource (lib "eagle-import") (part "TPPAD1-13"))
    )
    (comp (ref "U1")
      (value "TM4C129ENCPDT")
      (footprint "eagle-import:TQFP-128")
      (fields (field (name "GNUM") "G50-QF128-C1294-ALH"))
      (libsource (lib "eagle-import") (part "TM4C129ENCPDT"))
    )
    (comp (ref "U4")
      (value "TPS2052B_DRB_8")
      (footprint "eagle-import:DRB8_2P4X1P65")
      (fields
        (field (name "GENERIC_PART_NUMBER") "TPS2052B")
        (field (name "MANUFACTURER") "Texas Instruments")
        (field (name "MANUFACTURER_PART_NUMBER") "tps2052b_drb_8")
      )
      (libsource (lib "eagle-import") (part "TPS2052B_DRB_8"))
    )
    (comp (ref "U5")
      (value "TPS73733_DRV_6")
      (footprint "eagle-import:DRV6_1P6X1")
      (libsource (lib "eagle-import") (part "TPS73733_DRV_6"))
    )
    (comp (ref "WAKE")
      (value "SWITCH_TACTILE")
      (footprint "eagle-import:SWITCH_6MM_6MM_TE_CON_SMD")
      (libsource (lib "eagle-import") (part "SWITCH_TACTILE"))
    )
    (comp (ref "Y1")
      (value "25Mhz")
      (footprint "eagle-import:NDK3.2X2.5")
      (libsource (lib "eagle-import") (part "NX3225GA"))
    )
    (comp (ref "Y3")
      (value "CRYATL_32K_SMD")
      (footprint "eagle-import:CRYSTAL_32K_SMD")
      (libsource (lib "eagle-import") (part "CRYATL_32K_SMD"))
    )
    (comp (ref "C32")
      (value "3300pF")
      (footprint "eagle-import:C0603")
      (libsource (lib "eagle-import") (part "C-USC0603"))
    )
    (comp (ref "D1")
      (value "LEDCHIPLED_0603")
      (footprint "eagle-import:CHIPLED_0603")
      (libsource (lib "eagle-import") (part "LEDCHIPLED_0603"))
    )
    (comp (ref "D2")
      (value "LEDCHIPLED_0603")
      (footprint "eagle-import:CHIPLED_0603")
      (libsource (lib "eagle-import") (part "LEDCHIPLED_0603"))
    )
    (comp (ref "R18")
      (value "100")
      (footprint "eagle-import:R0402")
      (libsource (lib "eagle-import") (part "ek-tm4c129exl_R-US_R0402"))
    )
    (comp (ref "R27")
      (value "330")
      (footprint "eagle-import:R0402")
      (libsource (lib "eagle-import") (part "ek-tm4c129exl_R-US_R0402"))
    )
    (comp (ref "R33")
      (value "330")
      (footprint "eagle-import:R0402")
      (libsource (lib "eagle-import") (part "ek-tm4c129exl_R-US_R0402"))
    )
    (comp (ref "R52")
      (value "1M")
      (footprint "eagle-import:R0603")
      (libsource (lib "eagle-import") (part "R-US_R0603"))
    )
    (comp (ref "TP4")
      (value "TPPAD1-13")
      (footprint "eagle-import:P1-13")
      (libsource (lib "eagle-import") (part "TPPAD1-13"))
    )
    (comp (ref "TP5")
      (value "TPPAD1-13")
      (footprint "eagle-import:P1-13")
      (libsource (lib "eagle-import") (part "TPPAD1-13"))
    )
    (comp (ref "TP6")
      (value "TPPAD1-13")
      (footprint "eagle-import:P1-13")
      (libsource (lib "eagle-import") (part "TPPAD1-13"))
    )
    (comp (ref "TP7")
      (value "TPPAD1-13")
      (footprint "eagle-import:P1-13")
      (libsource (lib "eagle-import") (part "TPPAD1-13"))
    )
    (comp (ref "TP14")
      (value "TPPAD1-13")
      (footprint "eagle-import:P1-13")
      (libsource (lib "eagle-import") (part "TPPAD1-13"))
    )
    (comp (ref "TP15")
      (value "TPPAD1-13")
      (footprint "eagle-import:P1-13")
      (libsource (lib "eagle-import") (part "TPPAD1-13"))
    )
    (comp (ref "TP16")
      (value "TPPAD1-13")
      (footprint "eagle-import:P1-13")
      (libsource (lib "eagle-import") (part "TPPAD1-13"))
    )
    (comp (ref "TP17")
      (value "TPPAD1-13")
      (footprint "eagle-import:P1-13")
      (libsource (lib "eagle-import") (part "TPPAD1-13"))
    )
    (comp (ref "U2")
      (value "TPD4S012_DRY_6")
      (footprint "eagle-import:DRY6")
      (fields
        (field (name "GENERIC_PART_NUMBER") "TPD4S012")
        (field (name "MANUFACTURER") "Texas Instruments")
        (field (name "MANUFACTURER_PART_NUMBER") "tpd4s012_dry_6")
      )
      (libsource (lib "eagle-import") (part "TPD4S012_DRY_6"))
    )
    (comp (ref "U7")
      (value "CON_USB_HIROSE_MICRO_AB_ZX62D_AB_5P8")
      (footprint "eagle-import:CON_USB_MICRO_AB_HIROSE_ZX62D-AB-5P8")
      (fields (field (name "GNUM") "G20-USBU-THAB-CEB"))
      (libsource (lib "eagle-import") (part "CON_USB_HIROSE_MICRO_AB_ZX62D_AB_5P8"))
    )
    (comp (ref "USR_SW1")
      (value "SWITCH_TACTILE")
      (footprint "eagle-import:SWITCH_6MM_6MM_TE_CON_SMD")
      (libsource (lib "eagle-import") (part "SWITCH_TACTILE"))
    )
    (comp (ref "USR_SW2")
      (value "SWITCH_TACTILE")
      (footprint "eagle-import:SWITCH_6MM_6MM_TE_CON_SMD")
      (libsource (lib "eagle-import") (part "SWITCH_TACTILE"))
    )
    (comp (ref "C27")
      (value "0.1uF")
      (footprint "eagle-import:C0402")
      (libsource (lib "eagle-import") (part "ek-tm4c129exl_C-USC0402"))
    )
    (comp (ref "C28")
      (value "0.1uF")
      (footprint "eagle-import:C0402")
      (libsource (lib "eagle-import") (part "ek-tm4c129exl_C-USC0402"))
    )
    (comp (ref "C29")
      (value "0.1uF")
      (footprint "eagle-import:C0402")
      (libsource (lib "eagle-import") (part "ek-tm4c129exl_C-USC0402"))
    )
    (comp (ref "C30")
      (value "0.1uF")
      (footprint "eagle-import:C0402")
      (libsource (lib "eagle-import") (part "ek-tm4c129exl_C-USC0402"))
    )
    (comp (ref "X11")
      (value "TSW-149-02-S-D")
      (footprint "eagle-import:TSW-149-02-S-D")
      (fields
        (field (name "GNUM1") "G22-THRE-1x49-AAC")
        (field (name "GNUM2") "G22-THRA-1X49-AAC")
        (field (name "POPOP") "OMIT")
      )
      (libsource (lib "eagle-import") (part "TSW-149-02-S-D"))
    )
  )
  (nets
    (net (code "1") (name "+3V3") (class "Default")
      (node (ref "C10") (pin "1") (pinfunction "1_1") (pintype "passive"))
      (node (ref "C11") (pin "1") (pinfunction "1_1") (pintype "passive"))
      (node (ref "C12") (pin "1") (pinfunction "1_1") (pintype "passive"))
      (node (ref "C13") (pin "1") (pinfunction "1_1") (pintype "passive"))
      (node (ref "C23") (pin "1") (pinfunction "1_1") (pintype "passive"))
      (node (ref "C25") (pin "1") (pinfunction "1_1") (pintype "passive"))
      (node (ref "C27") (pin "1") (pinfunction "1_1") (pintype "passive"))
      (node (ref "C29") (pin "1") (pinfunction "1_1") (pintype "passive"))
      (node (ref "D0") (pin "A") (pinfunction "A_A") (pintype "passive"))
      (node (ref "JP2") (pin "1") (pinfunction "1_1") (pintype "passive"))
      (node (ref "JP3") (pin "1") (pinfunction "1_1") (pintype "passive"))
      (node (ref "R3") (pin "2") (pinfunction "2_2") (pintype "passive"))
      (node (ref "R4") (pin "1") (pinfunction "1_1") (pintype "passive"))
      (node (ref "R5") (pin "1") (pinfunction "1_1") (pintype "passive"))
      (node (ref "U20") (pin "P$11") (pinfunction "VDD0_P$11") (pintype "bidirectional"))
      (node (ref "U20") (pin "P$2") (pinfunction "VDDA_P$2") (pintype "bidirectional"))
      (node (ref "U20") (pin "P$26") (pinfunction "VDD1_P$26") (pintype "bidirectional"))
      (node (ref "U20") (pin "P$37") (pinfunction "VBAT_P$37") (pintype "bidirectional"))
      (node (ref "U20") (pin "P$42") (pinfunction "VDD2_P$42") (pintype "bidirectional"))
      (node (ref "U20") (pin "P$54") (pinfunction "VDD3_P$54") (pintype "bidirectional"))
      (node (ref "U21") (pin "1") (pinfunction "VTREF_1") (pintype "bidirectional"))
      (node (ref "U6") (pin "P1") (pinfunction "VTARGET_P1") (pintype "bidirectional"))
      (node (ref "X11") (pin "1") (pinfunction "1_1") (pintype "passive"))
      (node (ref "X11") (pin "98") (pinfunction "1_98") (pintype "passive"))
      (node (ref "X6") (pin "1") (pinfunction "1_1") (pintype "passive"))
      (node (ref "X8") (pin "1") (pinfunction "1_1") (pintype "passive"))
    )
    (net (code "2") (name "+5V") (class "Default")
      (node (ref "C21") (pin "1") (pinfunction "1_1") (pintype "passive"))
      (node (ref "C24") (pin "1") (pinfunction "1_1") (pintype "passive"))
      (node (ref "C26") (pin "1") (pinfunction "1_1") (pintype "passive"))
      (node (ref "C28") (pin "1") (pinfunction "1_1") (pintype "passive"))
      (node (ref "C30") (pin "1") (pinfunction "1_1") (pintype "passive"))
      (node (ref "R17") (pin "1") (pinfunction "1_1") (pintype "passive"))
      (node (ref "U4") (pin "7") (pinfunction "OUT1_7") (pintype "output"))
      (node (ref "U5") (pin "6") (pinfunction "IN_6") (pintype "input"))
      (node (ref "X11") (pin "2") (pinfunction "1_2") (pintype "passive"))
      (node (ref "X11") (pin "97") (pinfunction "1_97") (pintype "passive"))
      (node (ref "X6") (pin "2") (pinfunction "1_2") (pintype "passive"))
      (node (ref "X8") (pin "2") (pinfunction "1_2") (pintype "passive"))
    )
    (net (code "4") (name "BP2_A2.5") (class "Default")
      (node (ref "JP4") (pin "4") (pinfunction "4_4") (pintype "passive"))
      (node (ref "X6") (pin "9") (pinfunction "1_9") (pintype "passive"))
    )
    (net (code "5") (name "BP2_A2.6") (class "Default")
      (node (ref "JP5") (pin "4") (pinfunction "4_4") (pintype "passive"))
      (node (ref "X6") (pin "11") (pinfunction "1_11") (pintype "passive"))
    )
    (net (code "6") (name "DEBUG_ACTIVE") (class "Default")
      (node (ref "TP1") (pin "TP") (pinfunction "TP_TP") (pintype "input"))
      (node (ref "U20") (pin "P$64") (pinfunction "PD3_P$64") (pintype "bidirectional"))
    )
    (net (code "7") (name "DEBUG_PC0{slash}TCK{slash}SWCLK") (class "Default")
      (node (ref "R8") (pin "2") (pinfunction "2_2") (pintype "passive"))
      (node (ref "U20") (pin "P$19") (pinfunction "PA2_P$19") (pintype "bidirectional"))
      (node (ref "U20") (pin "P$30") (pinfunction "PF2_P$30") (pintype "bidirectional"))
      (node (ref "U6") (pin "P4") (pinfunction "TCK_P4") (pintype "bidirectional"))
      (node (ref "X1") (pin "9") (pinfunction "1_9") (pintype "passive"))
    )
    (net (code "8") (name "DEBUG_PC1{slash}TMS{slash}SWDIO") (class "Default")
      (node (ref "R10") (pin "2") (pinfunction "2_2") (pintype "passive"))
      (node (ref "U20") (pin "P$20") (pinfunction "PA3_P$20") (pintype "bidirectional"))
      (node (ref "U20") (pin "P$29") (pinfunction "PF1_P$29") (pintype "bidirectional"))
      (node (ref "U6") (pin "P2") (pinfunction "TMS_P2") (pintype "bidirectional"))
      (node (ref "X1") (pin "7") (pinfunction "1_7") (pintype "passive"))
    )
    (net (code "9") (name "DEBUG_PC2{slash}TDI") (class "Default")
      (node (ref "R11") (pin "2") (pinfunction "2_2") (pintype "passive"))
      (node (ref "U20") (pin "P$22") (pinfunction "PA5_P$22") (pintype "bidirectional"))
      (node (ref "U6") (pin "P8") (pinfunction "TDI_P8") (pintype "bidirectional"))
      (node (ref "X1") (pin "5") (pinfunction "1_5") (pintype "passive"))
    )
    (net (code "10") (name "DEBUG_PC3{slash}TDO{slash}SWO") (class "Default")
      (node (ref "R15") (pin "2") (pinfunction "2_2") (pintype "passive"))
      (node (ref "U20") (pin "P$21") (pinfunction "PA4_P$21") (pintype "bidirectional"))
      (node (ref "U20") (pin "P$53") (pinfunction "PD6_P$53") (pintype "bidirectional"))
      (node (ref "U6") (pin "P6") (pinfunction "TDO_P6") (pintype "bidirectional"))
      (node (ref "X1") (pin "3") (pinfunction "1_3") (pintype "passive"))
    )
    (net (code "11") (name "DEBUG_VBUS") (class "Default")
      (node (ref "JP1") (pin "5") (pinfunction "5_5") (pintype "passive"))
      (node (ref "R28") (pin "2") (pinfunction "2_2") (pintype "passive"))
      (node (ref "U22") (pin "P1") (pinfunction "VBUS_P1") (pintype "bidirectional"))
      (node (ref "U3") (pin "6") (pinfunction "VBUS_6") (pintype "passive"))
    )
    (net (code "12") (name "EN0RXI_N") (class "Default")
      (node (ref "R21") (pin "2") (pinfunction "2_2") (pintype "passive"))
      (node (ref "U1") (pin "P$53") (pinfunction "EN0RXIN_P$53") (pintype "bidirectional"))
      (node (ref "U10") (pin "P$8") (pinfunction "P$8_P$8") (pintype "bidirectional"))
    )
    (net (code "13") (name "EN0RXI_P") (class "Default")
      (node (ref "R22") (pin "2") (pinfunction "2_2") (pintype "passive"))
      (node (ref "U1") (pin "P$54") (pinfunction "EN0RXIP_P$54") (pintype "bidirectional"))
      (node (ref "U10") (pin "P$6") (pinfunction "P$6_P$6") (pintype "bidirectional"))
    )
    (net (code "14") (name "EN0TXO_N") (class "Default")
      (node (ref "R23") (pin "2") (pinfunction "2_2") (pintype "passive"))
      (node (ref "U1") (pin "P$56") (pinfunction "EN0TXON_P$56") (pintype "bidirectional"))
      (node (ref "U10") (pin "P$3") (pinfunction "P$3_P$3") (pintype "bidirectional"))
    )
    (net (code "15") (name "EN0TXO_P") (class "Default")
      (node (ref "R24") (pin "2") (pinfunction "2_2") (pintype "passive"))
      (node (ref "U1") (pin "P$57") (pinfunction "EN0TXOP_P$57") (pintype "bidirectional"))
      (node (ref "U10") (pin "P$1") (pinfunction "P$1_P$1") (pintype "bidirectional"))
    )
    (net (code "16") (name "GND") (class "Default")
      (node (ref "C10") (pin "2") (pinfunction "2_2") (pintype "passive"))
      (node (ref "C11") (pin "2") (pinfunction "2_2") (pintype "passive"))
      (node (ref "C12") (pin "2") (pinfunction "2_2") (pintype "passive"))
      (node (ref "C13") (pin "2") (pinfunction "2_2") (pintype "passive"))
      (node (ref "C14") (pin "2") (pinfunction "2_2") (pintype "passive"))
      (node (ref "C15") (pin "2") (pinfunction "2_2") (pintype "passive"))
      (node (ref "C16") (pin "2") (pinfunction "2_2") (pintype "passive"))
      (node (ref "C17") (pin "2") (pinfunction "2_2") (pintype "passive"))
      (node (ref "C18") (pin "2") (pinfunction "2_2") (pintype "passive"))
      (node (ref "C19") (pin "2") (pinfunction "2_2") (pintype "passive"))
      (node (ref "C2") (pin "2") (pinfunction "2_2") (pintype "passive"))
      (node (ref "C20") (pin "2") (pinfunction "2_2") (pintype "passive"))
      (node (ref "C21") (pin "2") (pinfunction "2_2") (pintype "passive"))
      (node (ref "C22") (pin "2") (pinfunction "2_2") (pintype "passive"))
      (node (ref "C23") (pin "2") (pinfunction "2_2") (pintype "passive"))
      (node (ref "C24") (pin "2") (pinfunction "2_2") (pintype "passive"))
      (node (ref "C25") (pin "2") (pinfunction "2_2") (pintype "passive"))
      (node (ref "C26") (pin "2") (pinfunction "2_2") (pintype "passive"))
      (node (ref "C27") (pin "2") (pinfunction "2_2") (pintype "passive"))
      (node (ref "C28") (pin "2") (pinfunction "2_2") (pintype "passive"))
      (node (ref "C29") (pin "2") (pinfunction "2_2") (pintype "passive"))
      (node (ref "C3") (pin "2") (pinfunction "2_2") (pintype "passive"))
      (node (ref "C30") (pin "2") (pinfunction "2_2") (pintype "passive"))
      (node (ref "C31") (pin "2") (pinfunction "2_2") (pintype "passive"))
      (node (ref "C32") (pin "2") (pinfunction "2_2") (pintype "passive"))
      (node (ref "C33") (pin "2") (pinfunction "2_2") (pintype "passive"))
      (node (ref "C4") (pin "2") (pinfunction "2_2") (pintype "passive"))
      (node (ref "C40") (pin "2") (pinfunction "2_2") (pintype "passive"))
      (node (ref "C41") (pin "2") (pinfunction "2_2") (pintype "passive"))
      (node (ref "C42") (pin "2") (pinfunction "2_2") (pintype "passive"))
      (node (ref "C43") (pin "2") (pinfunction "2_2") (pintype "passive"))
      (node (ref "C44") (pin "2") (pinfunction "2_2") (pintype "passive"))
      (node (ref "C45") (pin "2") (pinfunction "2_2") (pintype "passive"))
      (node (ref "C46") (pin "2") (pinfunction "2_2") (pintype "passive"))
      (node (ref "C47") (pin "2") (pinfunction "2_2") (pintype "passive"))
      (node (ref "C48") (pin "2") (pinfunction "2_2") (pintype "passive"))
      (node (ref "C5") (pin "2") (pinfunction "2_2") (pintype "passive"))
      (node (ref "C6") (pin "2") (pinfunction "2_2") (pintype "passive"))
      (node (ref "C7") (pin "2") (pinfunction "2_2") (pintype "passive"))
      (node (ref "C8") (pin "2") (pinfunction "2_2") (pintype "passive"))
      (node (ref "C9") (pin "2") (pinfunction "2_2") (pintype "passive"))
      (node (ref "R12") (pin "2") (pinfunction "2_2") (pintype "passive"))
      (node (ref "R13") (pin "2") (pinfunction "2_2") (pintype "passive"))
      (node (ref "R14") (pin "2") (pinfunction "2_2") (pintype "passive"))
      (node (ref "R25") (pin "2") (pinfunction "2_2") (pintype "passive"))
      (node (ref "R26") (pin "2") (pinfunction "2_2") (pintype "passive"))
      (node (ref "R27") (pin "1") (pinfunction "1_1") (pintype "passive"))
      (node (ref "R29") (pin "1") (pinfunction "1_1") (pintype "passive"))
      (node (ref "R30") (pin "1") (pinfunction "1_1") (pintype "passive"))
      (node (ref "R31") (pin "1") (pinfunction "1_1") (pintype "passive"))
      (node (ref "R33") (pin "1") (pinfunction "1_1") (pintype "passive"))
      (node (ref "R34") (pin "1") (pinfunction "1_1") (pintype "passive"))
      (node (ref "R47") (pin "1") (pinfunction "1_1") (pintype "passive"))
      (node (ref "R52") (pin "1") (pinfunction "1_1") (pintype "passive"))
      (node (ref "R9") (pin "1") (pinfunction "1_1") (pintype "passive"))
      (node (ref "RESET") (pin "P$1") (pinfunction "0_P$1") (pintype "passive"))
      (node (ref "RESET") (pin "P$2") (pinfunction "0_P$2") (pintype "passive"))
      (node (ref "TP14") (pin "TP") (pinfunction "TP_TP") (pintype "input"))
      (node (ref "TP15") (pin "TP") (pinfunction "TP_TP") (pintype "input"))
      (node (ref "TP16") (pin "TP") (pinfunction "TP_TP") (pintype "input"))
      (node (ref "TP17") (pin "TP") (pinfunction "TP_TP") (pintype "input"))
      (node (ref "U1") (pin "P$10") (pinfunction "GNDA_P$10") (pintype "bidirectional"))
      (node (ref "U1") (pin "P$114") (pinfunction "GND_P$114") (pintype "bidirectional"))
      (node (ref "U1") (pin "P$17") (pinfunction "GND_P$17") (pintype "bidirectional"))
      (node (ref "U1") (pin "P$48") (pinfunction "GND_P$48") (pintype "bidirectional"))
      (node (ref "U1") (pin "P$55") (pinfunction "GND_P$55") (pintype "bidirectional"))
      (node (ref "U1") (pin "P$58") (pinfunction "GND_P$58") (pintype "bidirectional"))
      (node (ref "U1") (pin "P$80") (pinfunction "GND_P$80") (pintype "bidirectional"))
      (node (ref "U2") (pin "4") (pinfunction "GND_4") (pintype "power_in"))
      (node (ref "U20") (pin "P$12") (pinfunction "GND0_P$12") (pintype "bidirectional"))
      (node (ref "U20") (pin "P$27") (pinfunction "GND1_P$27") (pintype "bidirectional"))
      (node (ref "U20") (pin "P$3") (pinfunction "GNDA_P$3") (pintype "bidirectional"))
      (node (ref "U20") (pin "P$32") (pinfunction "~{WAKE}_P$32") (pintype "bidirectional"))
      (node (ref "U20") (pin "P$34") (pinfunction "XOSC0_P$34") (pintype "bidirectional"))
      (node (ref "U20") (pin "P$35") (pinfunction "GNDX_P$35") (pintype "bidirectional"))
      (node (ref "U20") (pin "P$39") (pinfunction "GND2_P$39") (pintype "bidirectional"))
      (node (ref "U20") (pin "P$55") (pinfunction "GND3_P$55") (pintype "bidirectional"))
      (node (ref "U21") (pin "3") (pinfunction "GND_3") (pintype "bidirectional"))
      (node (ref "U21") (pin "5") (pinfunction "NC_5") (pintype "bidirectional"))
      (node (ref "U21") (pin "9") (pinfunction "~{TRST}_9") (pintype "bidirectional"))
      (node (ref "U22") (pin "P5") (pinfunction "GND_P5") (pintype "bidirectional"))
      (node (ref "U3") (pin "4") (pinfunction "GND_4") (pintype "power_in"))
      (node (ref "U4") (pin "1") (pinfunction "GND_1") (pintype "power_in"))
      (node (ref "U4") (pin "9") (pinfunction "EPAD_9") (pintype "passive"))
      (node (ref "U4") (pin "V") (pinfunction "VIA_V") (pintype "bidirectional"))
      (node (ref "U4") (pin "V_2") (pinfunction "VIA_V_2") (pintype "bidirectional"))
      (node (ref "U4") (pin "V_3") (pinfunction "VIA_V_3") (pintype "bidirectional"))
      (node (ref "U4") (pin "V_4") (pinfunction "VIA_V_4") (pintype "bidirectional"))
      (node (ref "U4") (pin "V_5") (pinfunction "VIA_V_5") (pintype "bidirectional"))
      (node (ref "U4") (pin "V_6") (pinfunction "VIA_V_6") (pintype "bidirectional"))
      (node (ref "U5") (pin "3") (pinfunction "GND_3") (pintype "power_in"))
      (node (ref "U5") (pin "7") (pinfunction "EPAD_7") (pintype "passive"))
      (node (ref "U5") (pin "V") (pinfunction "VIA_V") (pintype "bidirectional"))
      (node (ref "U5") (pin "V_2") (pinfunction "VIA_V_2") (pintype "bidirectional"))
      (node (ref "U6") (pin "P5") (pinfunction "GND_P5") (pintype "bidirectional"))
      (node (ref "U6") (pin "P9") (pinfunction "GND1_P9") (pintype "bidirectional"))
      (node (ref "U7") (pin "P5") (pinfunction "GND_P5") (pintype "bidirectional"))
      (node (ref "USR_SW1") (pin "P$3") (pinfunction "1_P$3") (pintype "passive"))
      (node (ref "USR_SW1") (pin "P$4") (pinfunction "1_P$4") (pintype "passive"))
      (node (ref "USR_SW2") (pin "P$3") (pinfunction "1_P$3") (pintype "passive"))
      (node (ref "USR_SW2") (pin "P$4") (pinfunction "1_P$4") (pintype "passive"))
      (node (ref "WAKE") (pin "P$3") (pinfunction "1_P$3") (pintype "passive"))
      (node (ref "WAKE") (pin "P$4") (pinfunction "1_P$4") (pintype "passive"))
      (node (ref "X11") (pin "3") (pinfunction "1_3") (pintype "passive"))
      (node (ref "X11") (pin "35") (pinfunction "1_35") (pintype "passive"))
      (node (ref "X11") (pin "36") (pinfunction "1_36") (pintype "passive"))
      (node (ref "X11") (pin "4") (pinfunction "1_4") (pintype "passive"))
      (node (ref "X11") (pin "61") (pinfunction "1_61") (pintype "passive"))
      (node (ref "X11") (pin "62") (pinfunction "1_62") (pintype "passive"))
      (node (ref "X11") (pin "96") (pinfunction "1_96") (pintype "passive"))
      (node (ref "X6") (pin "4") (pinfunction "1_4") (pintype "passive"))
      (node (ref "X7") (pin "2") (pinfunction "1_2") (pintype "passive"))
      (node (ref "X8") (pin "4") (pinfunction "1_4") (pintype "passive"))
      (node (ref "X9") (pin "2") (pinfunction "1_2") (pintype "passive"))
    )
    (net (code "17") (name "ICDI_RESET") (class "Default")
      (node (ref "C2") (pin "1") (pinfunction "1_1") (pintype "passive"))
      (node (ref "R3") (pin "1") (pinfunction "1_1") (pintype "passive"))
      (node (ref "U20") (pin "P$38") (pinfunction "~{RESET}_P$38") (pintype "bidirectional"))
      (node (ref "U21") (pin "10") (pinfunction "RESET_10") (pintype "bidirectional"))
    )
    (net (code "18") (name "ICDI_TCK") (class "Default")
      (node (ref "R4") (pin "2") (pinfunction "2_2") (pintype "passive"))
      (node (ref "U20") (pin "P$52") (pinfunction "PC0/TCK_P$52") (pintype "bidirectional"))
      (node (ref "U21") (pin "4") (pinfunction "TCK_4") (pintype "bidirectional"))
    )
    (net (code "19") (name "ICDI_TDI") (class "Default")
      (node (ref "U20") (pin "P$50") (pinfunction "PC2/TDI_P$50") (pintype "bidirectional"))
      (node (ref "U21") (pin "8") (pinfunction "TDI_8") (pintype "bidirectional"))
    )
    (net (code "20") (name "ICDI_TDO") (class "Default")
      (node (ref "U20") (pin "P$49") (pinfunction "PC3/TDO_P$49") (pintype "bidirectional"))
      (node (ref "U21") (pin "6") (pinfunction "TDO_6") (pintype "bidirectional"))
    )
    (net (code "21") (name "ICDI_TMS") (class "Default")
      (node (ref "R5") (pin "2") (pinfunction "2_2") (pintype "passive"))
      (node (ref "U20") (pin "P$51") (pinfunction "PC1/TMS_P$51") (pintype "bidirectional"))
      (node (ref "U21") (pin "2") (pinfunction "TMS_2") (pintype "bidirectional"))
    )
    (net (code "22") (name "ICDI_USBD_N") (class "Default")
      (node (ref "U20") (pin "P$43") (pinfunction "PD4_P$43") (pintype "bidirectional"))
      (node (ref "U22") (pin "P2") (pinfunction "DM_P2") (pintype "bidirectional"))
      (node (ref "U3") (pin "2") (pinfunction "D-_2") (pintype "passive"))
    )
    (net (code "23") (name "ICDI_USBD_P") (class "Default")
      (node (ref "U20") (pin "P$44") (pinfunction "PD5_P$44") (pintype "bidirectional"))
      (node (ref "U22") (pin "P3") (pinfunction "DP_P3") (pintype "bidirectional"))
      (node (ref "U3") (pin "1") (pinfunction "D+_1") (pintype "passive"))
    )
    (net (code "24") (name "ICDI_VDDC") (class "Default")
      (node (ref "C5") (pin "1") (pinfunction "1_1") (pintype "passive"))
      (node (ref "C6") (pin "1") (pinfunction "1_1") (pintype "passive"))
      (node (ref "C7") (pin "1") (pinfunction "1_1") (pintype "passive"))
      (node (ref "U20") (pin "P$25") (pinfunction "VDDC0_P$25") (pintype "bidirectional"))
      (node (ref "U20") (pin "P$56") (pinfunction "VDDC1_P$56") (pintype "bidirectional"))
    )
    (net (code "25") (name "MCU_3V3") (class "Default")
      (node (ref "C16") (pin "1") (pinfunction "1_1") (pintype "passive"))
      (node (ref "C17") (pin "1") (pinfunction "1_1") (pintype "passive"))
      (node (ref "C18") (pin "1") (pinfunction "1_1") (pintype "passive"))
      (node (ref "C22") (pin "1") (pinfunction "1_1") (pintype "passive"))
      (node (ref "C40") (pin "1") (pinfunction "1_1") (pintype "passive"))
      (node (ref "C41") (pin "1") (pinfunction "1_1") (pintype "passive"))
      (node (ref "C42") (pin "1") (pinfunction "1_1") (pintype "passive"))
      (node (ref "C43") (pin "1") (pinfunction "1_1") (pintype "passive"))
      (node (ref "JP2") (pin "2") (pinfunction "2_2") (pintype "passive"))
      (node (ref "R1") (pin "1") (pinfunction "1_1") (pintype "passive"))
      (node (ref "R2") (pin "1") (pinfunction "1_1") (pintype "passive"))
      (node (ref "R21") (pin "1") (pinfunction "1_1") (pintype "passive"))
      (node (ref "R22") (pin "1") (pinfunction "1_1") (pintype "passive"))
      (node (ref "R23") (pin "1") (pinfunction "1_1") (pintype "passive"))
      (node (ref "R24") (pin "1") (pinfunction "1_1") (pintype "passive"))
      (node (ref "R39") (pin "2") (pinfunction "2_2") (pintype "passive"))
      (node (ref "R41") (pin "2") (pinfunction "2_2") (pintype "passive"))
      (node (ref "R44") (pin "1") (pinfunction "1_1") (pintype "passive"))
      (node (ref "U1") (pin "P$101") (pinfunction "VDD_P$101") (pintype "bidirectional"))
      (node (ref "U1") (pin "P$113") (pinfunction "VDD_P$113") (pintype "bidirectional"))
      (node (ref "U1") (pin "P$122") (pinfunction "VDD_P$122") (pintype "bidirectional"))
      (node (ref "U1") (pin "P$16") (pinfunction "VDD_P$16") (pintype "bidirectional"))
      (node (ref "U1") (pin "P$26") (pinfunction "VDD_P$26") (pintype "bidirectional"))
      (node (ref "U1") (pin "P$28") (pinfunction "VDD_P$28") (pintype "bidirectional"))
      (node (ref "U1") (pin "P$39") (pinfunction "VDD_P$39") (pintype "bidirectional"))
      (node (ref "U1") (pin "P$47") (pinfunction "VDD_P$47") (pintype "bidirectional"))
      (node (ref "U1") (pin "P$51") (pinfunction "VDD_P$51") (pintype "bidirectional"))
      (node (ref "U1") (pin "P$52") (pinfunction "VDD_P$52") (pintype "bidirectional"))
      (node (ref "U1") (pin "P$69") (pinfunction "VDD_P$69") (pintype "bidirectional"))
      (node (ref "U1") (pin "P$7") (pinfunction "VDD_P$7") (pintype "bidirectional"))
      (node (ref "U1") (pin "P$79") (pinfunction "VDD_P$79") (pintype "bidirectional"))
      (node (ref "U1") (pin "P$8") (pinfunction "VDDA_P$8") (pintype "bidirectional"))
      (node (ref "U1") (pin "P$90") (pinfunction "VDD_P$90") (pintype "bidirectional"))
      (node (ref "U10") (pin "P$2") (pinfunction "P$2_P$2") (pintype "bidirectional"))
      (node (ref "U10") (pin "P$7") (pinfunction "P$7_P$7") (pintype "bidirectional"))
    )
    (net (code "26") (name "Net-(C1-Pad1)") (class "Default")
      (node (ref "C1") (pin "1") (pinfunction "1_1") (pintype "passive"))
      (node (ref "R32") (pin "1") (pinfunction "1_1") (pintype "passive"))
      (node (ref "R43") (pin "1") (pinfunction "1_1") (pintype "passive"))
      (node (ref "R45") (pin "1") (pinfunction "1_1") (pintype "passive"))
      (node (ref "R46") (pin "1") (pinfunction "1_1") (pintype "passive"))
    )
    (net (code "27") (name "Net-(C1-Pad2)") (class "Default")
      (node (ref "C1") (pin "2") (pinfunction "2_2") (pintype "passive"))
      (node (ref "C31") (pin "1") (pinfunction "1_1") (pintype "passive"))
      (node (ref "R47") (pin "2") (pinfunction "2_2") (pintype "passive"))
      (node (ref "U14") (pin "10") (pinfunction "CHASSIS_10") (pintype "bidirectional"))
      (node (ref "U14") (pin "9") (pinfunction "CHASSIS_9") (pintype "bidirectional"))
    )
    (net (code "28") (name "Net-(C14-Pad1)") (class "Default")
      (node (ref "C14") (pin "1") (pinfunction "1_1") (pintype "passive"))
      (node (ref "C15") (pin "1") (pinfunction "1_1") (pintype "passive"))
      (node (ref "C4") (pin "1") (pinfunction "1_1") (pintype "passive"))
      (node (ref "TP12") (pin "TP") (pinfunction "TP_TP") (pintype "input"))
      (node (ref "U1") (pin "P$115") (pinfunction "VDDC_P$115") (pintype "bidirectional"))
      (node (ref "U1") (pin "P$87") (pinfunction "VDDC_P$87") (pintype "bidirectional"))
    )
    (net (code "29") (name "Net-(D0-PadC)") (class "Default")
      (node (ref "D0") (pin "C") (pinfunction "C_C") (pintype "passive"))
      (node (ref "R9") (pin "2") (pinfunction "2_2") (pintype "passive"))
    )
    (net (code "30") (name "Net-(D1-PadC)") (class "Default")
      (node (ref "D1") (pin "C") (pinfunction "C_C") (pintype "passive"))
      (node (ref "R33") (pin "2") (pinfunction "2_2") (pintype "passive"))
    )
    (net (code "31") (name "Net-(D2-PadC)") (class "Default")
      (node (ref "D2") (pin "C") (pinfunction "C_C") (pintype "passive"))
      (node (ref "R27") (pin "2") (pinfunction "2_2") (pintype "passive"))
    )
    (net (code "32") (name "Net-(D3-PadC)") (class "Default")
      (node (ref "D3") (pin "C") (pinfunction "C_C") (pintype "passive"))
      (node (ref "R31") (pin "2") (pinfunction "2_2") (pintype "passive"))
    )
    (net (code "33") (name "Net-(D4-PadC)") (class "Default")
      (node (ref "D4") (pin "C") (pinfunction "C_C") (pintype "passive"))
      (node (ref "R30") (pin "2") (pinfunction "2_2") (pintype "passive"))
    )
    (net (code "34") (name "Net-(R32-Pad2)") (class "Default")
      (node (ref "R32") (pin "2") (pinfunction "2_2") (pintype "passive"))
      (node (ref "U10") (pin "P$15") (pinfunction "P$15_P$15") (pintype "bidirectional"))
    )
    (net (code "35") (name "Net-(R38-Pad1)") (class "Default")
      (node (ref "R38") (pin "1") (pinfunction "1_1") (pintype "passive"))
      (node (ref "R39") (pin "1") (pinfunction "1_1") (pintype "passive"))
      (node (ref "R42") (pin "1") (pinfunction "1_1") (pintype "passive"))
      (node (ref "TP11") (pin "TP") (pinfunction "TP_TP") (pintype "input"))
    )
    (net (code "36") (name "Net-(R43-Pad2)") (class "Default")
      (node (ref "R43") (pin "2") (pinfunction "2_2") (pintype "passive"))
      (node (ref "U10") (pin "P$10") (pinfunction "P$10_P$10") (pintype "bidirectional"))
    )
    (net (code "37") (name "Net-(U1B-OSC0)") (class "Default")
      (node (ref "C44") (pin "1") (pinfunction "1_1") (pintype "passive"))
      (node (ref "U1") (pin "P$88") (pinfunction "OSC0_P$88") (pintype "bidirectional"))
      (node (ref "Y1") (pin "P$3") (pinfunction "OSC1_P$3") (pintype "bidirectional"))
    )
    (net (code "38") (name "Net-(U1B-OSC1)") (class "Default")
      (node (ref "R49") (pin "2") (pinfunction "2_2") (pintype "passive"))
      (node (ref "U1") (pin "P$89") (pinfunction "OSC1_P$89") (pintype "bidirectional"))
    )
    (net (code "39") (name "Net-(U1B-VBAT)") (class "Default")
      (node (ref "C3") (pin "1") (pinfunction "1_1") (pintype "passive"))
      (node (ref "R38") (pin "2") (pinfunction "2_2") (pintype "passive"))
      (node (ref "U1") (pin "P$68") (pinfunction "VBAT_P$68") (pintype "bidirectional"))
    )
    (net (code "40") (name "Net-(U1B-XOSC0)") (class "Default")
      (node (ref "C48") (pin "1") (pinfunction "1_1") (pintype "passive"))
      (node (ref "U1") (pin "P$66") (pinfunction "XOSC0_P$66") (pintype "bidirectional"))
      (node (ref "Y3") (pin "P$1") (pinfunction "P$1_P$1") (pintype "bidirectional"))
    )
    (net (code "41") (name "Net-(U1B-XOSC1)") (class "Default")
      (node (ref "C47") (pin "1") (pinfunction "1_1") (pintype "passive"))
      (node (ref "U1") (pin "P$67") (pinfunction "XOSC1_P$67") (pintype "bidirectional"))
      (node (ref "Y3") (pin "P$2") (pinfunction "P$2_P$2") (pintype "bidirectional"))
    )
    (net (code "42") (name "Net-(U1B-~{HIB})") (class "Default")
      (node (ref "TP9") (pin "TP") (pinfunction "TP_TP") (pintype "input"))
      (node (ref "U1") (pin "P$65") (pinfunction "~{HIB}_P$65") (pintype "bidirectional"))
    )
    (net (code "43") (name "Net-(U1B-~{RESET})") (class "Default")
      (node (ref "C46") (pin "1") (pinfunction "1_1") (pintype "passive"))
      (node (ref "R44") (pin "2") (pinfunction "2_2") (pintype "passive"))
      (node (ref "R51") (pin "2") (pinfunction "2_2") (pintype "passive"))
      (node (ref "U1") (pin "P$70") (pinfunction "~{RESET}_P$70") (pintype "bidirectional"))
    )
    (net (code "44") (name "Net-(U4-*EN1)") (class "Default")
      (node (ref "R26") (pin "1") (pinfunction "1_1") (pintype "passive"))
      (node (ref "R35") (pin "2") (pinfunction "2_2") (pintype "passive"))
      (node (ref "U4") (pin "3") (pinfunction "*EN1_3") (pintype "input"))
    )
    (net (code "45") (name "Net-(U4-*OC1)") (class "Default")
      (node (ref "R36") (pin "1") (pinfunction "1_1") (pintype "passive"))
      (node (ref "TP8") (pin "TP") (pinfunction "TP_TP") (pintype "input"))
      (node (ref "U4") (pin "8") (pinfunction "*OC1_8") (pintype "output"))
    )
    (net (code "46") (name "Net-(U5-EN)") (class "Default")
      (node (ref "R17") (pin "2") (pinfunction "2_2") (pintype "passive"))
      (node (ref "TP3") (pin "TP") (pinfunction "TP_TP") (pintype "input"))
      (node (ref "U5") (pin "4") (pinfunction "EN_4") (pintype "passive"))
    )
    (net (code "47") (name "Net-(U5-NR{slash}FB)") (class "Default")
      (node (ref "C19") (pin "1") (pinfunction "1_1") (pintype "passive"))
      (node (ref "R48") (pin "1") (pinfunction "1_1") (pintype "passive"))
      (node (ref "U5") (pin "2") (pinfunction "NR/FB_2") (pintype "bidirectional"))
    )
    (net (code "48") (name "Net-(U5-OUT)") (class "Default")
      (node (ref "C20") (pin "1") (pinfunction "1_1") (pintype "passive"))
      (node (ref "JP3") (pin "2") (pinfunction "2_2") (pintype "passive"))
      (node (ref "R48") (pin "2") (pinfunction "2_2") (pintype "passive"))
      (node (ref "U5") (pin "1") (pinfunction "OUT_1") (pintype "output"))
    )
    (net (code "49") (name "Net-(U6-~{EXTDBG})") (class "Default")
      (node (ref "R40") (pin "2") (pinfunction "2_2") (pintype "passive"))
      (node (ref "U6") (pin "P3") (pinfunction "~{EXTDBG}_P3") (pintype "bidirectional"))
    )
    (net (code "50") (name "Net-(U7B-S1)") (class "Default")
      (node (ref "C32") (pin "1") (pinfunction "1_1") (pintype "passive"))
      (node (ref "R52") (pin "2") (pinfunction "2_2") (pintype "passive"))
      (node (ref "U7") (pin "P$1") (pinfunction "S1_P$1") (pintype "passive"))
      (node (ref "U7") (pin "P$2") (pinfunction "S2_P$2") (pintype "passive"))
      (node (ref "U7") (pin "P$3") (pinfunction "S3_P$3") (pintype "passive"))
      (node (ref "U7") (pin "P$4") (pinfunction "S4_P$4") (pintype "passive"))
      (node (ref "U7") (pin "P$5") (pinfunction "S5_P$5") (pintype "passive"))
      (node (ref "U7") (pin "P$6") (pinfunction "S6_P$6") (pintype "passive"))
    )
    (net (code "51") (name "Net-(U13-P$1)") (class "Default")
      (node (ref "U10") (pin "P$16") (pinfunction "P$16_P$16") (pintype "bidirectional"))
      (node (ref "U13") (pin "1") (pinfunction "P$1_1") (pintype "bidirectional"))
      (node (ref "U13") (pin "8") (pinfunction "P$8_8") (pintype "bidirectional"))
      (node (ref "U14") (pin "1") (pinfunction "TX+_1") (pintype "bidirectional"))
    )
    (net (code "52") (name "Net-(U13-P$2)") (class "Default")
      (node (ref "U10") (pin "P$14") (pinfunction "P$14_P$14") (pintype "bidirectional"))
      (node (ref "U13") (pin "2") (pinfunction "P$2_2") (pintype "bidirectional"))
      (node (ref "U13") (pin "7") (pinfunction "P$7_7") (pintype "bidirectional"))
      (node (ref "U14") (pin "2") (pinfunction "TX-_2") (pintype "bidirectional"))
    )
    (net (code "53") (name "Net-(U13-P$3)") (class "Default")
      (node (ref "U10") (pin "P$11") (pinfunction "P$11_P$11") (pintype "bidirectional"))
      (node (ref "U13") (pin "3") (pinfunction "P$3_3") (pintype "bidirectional"))
      (node (ref "U13") (pin "6") (pinfunction "P$6_6") (pintype "bidirectional"))
      (node (ref "U14") (pin "3") (pinfunction "RX+_3") (pintype "bidirectional"))
    )
    (net (code "54") (name "Net-(U13-P$4)") (class "Default")
      (node (ref "U10") (pin "P$9") (pinfunction "P$9_P$9") (pintype "bidirectional"))
      (node (ref "U13") (pin "4") (pinfunction "P$4_4") (pintype "bidirectional"))
      (node (ref "U13") (pin "5") (pinfunction "P$5_5") (pintype "bidirectional"))
      (node (ref "U14") (pin "6") (pinfunction "RX-_6") (pintype "bidirectional"))
    )
    (net (code "55") (name "Net-(U14-TERM1A)") (class "Default")
      (node (ref "R45") (pin "2") (pinfunction "2_2") (pintype "passive"))
      (node (ref "U14") (pin "4") (pinfunction "TERM1A_4") (pintype "bidirectional"))
      (node (ref "U14") (pin "5") (pinfunction "TERM1B_5") (pintype "bidirectional"))
    )
    (net (code "56") (name "Net-(U14-TERM2A)") (class "Default")
      (node (ref "R46") (pin "2") (pinfunction "2_2") (pintype "passive"))
      (node (ref "U14") (pin "7") (pinfunction "TERM2A_7") (pintype "bidirectional"))
      (node (ref "U14") (pin "8") (pinfunction "TERM2B_8") (pintype "bidirectional"))
    )
    (net (code "57") (name "Net-(U20-OSC0)") (class "Default")
      (node (ref "C9") (pin "1") (pinfunction "1_1") (pintype "passive"))
      (node (ref "U20") (pin "P$40") (pinfunction "OSC0_P$40") (pintype "bidirectional"))
      (node (ref "Y2") (pin "P$1") (pinfunction "OSC0_P$1") (pintype "bidirectional"))
    )
    (net (code "58") (name "Net-(U20-OSC1)") (class "Default")
      (node (ref "R50") (pin "1") (pinfunction "1_1") (pintype "passive"))
      (node (ref "U20") (pin "P$41") (pinfunction "OSC1_P$41") (pintype "bidirectional"))
    )
    (net (code "59") (name "Net-(U20-PB1)") (class "Default")
      (node (ref "R28") (pin "1") (pinfunction "1_1") (pintype "passive"))
      (node (ref "R29") (pin "2") (pinfunction "2_2") (pintype "passive"))
      (node (ref "U20") (pin "P$46") (pinfunction "PB1_P$46") (pintype "bidirectional"))
    )
    (net (code "60") (name "Net-(U22B-S1)") (class "Default")
      (node (ref "C33") (pin "1") (pinfunction "1_1") (pintype "passive"))
      (node (ref "R34") (pin "2") (pinfunction "2_2") (pintype "passive"))
      (node (ref "U22") (pin "P10") (pinfunction "S5_P10") (pintype "passive"))
      (node (ref "U22") (pin "P11") (pinfunction "S6_P11") (pintype "passive"))
      (node (ref "U22") (pin "P6") (pinfunction "S1_P6") (pintype "passive"))
      (node (ref "U22") (pin "P7") (pinfunction "S2_P7") (pintype "passive"))
      (node (ref "U22") (pin "P8") (pinfunction "S3_P8") (pintype "passive"))
      (node (ref "U22") (pin "P9") (pinfunction "S4_P9") (pintype "passive"))
    )
    (net (code "61") (name "Net-(Y1-OSC0)") (class "Default")
      (node (ref "C45") (pin "1") (pinfunction "1_1") (pintype "passive"))
      (node (ref "R49") (pin "1") (pinfunction "1_1") (pintype "passive"))
      (node (ref "Y1") (pin "P$1") (pinfunction "OSC0_P$1") (pintype "bidirectional"))
    )
    (net (code "62") (name "Net-(Y2-OSC1)") (class "Default")
      (node (ref "C8") (pin "1") (pinfunction "1_1") (pintype "passive"))
      (node (ref "R50") (pin "2") (pinfunction "2_2") (pintype "passive"))
      (node (ref "Y2") (pin "P$3") (pinfunction "OSC1_P$3") (pintype "bidirectional"))
    )
    (net (code "63") (name "PA0") (class "Default")
      (node (ref "JP4") (pin "2") (pinfunction "2_2") (pintype "passive"))
      (node (ref "U1") (pin "P$33") (pinfunction "PA0_P$33") (pintype "bidirectional"))
      (node (ref "X11") (pin "74") (pinfunction "1_74") (pintype "passive"))
    )
    (net (code "64") (name "PA1") (class "Default")
      (node (ref "JP5") (pin "2") (pinfunction "2_2") (pintype "passive"))
      (node (ref "U1") (pin "P$34") (pinfunction "PA1_P$34") (pintype "bidirectional"))
      (node (ref "X11") (pin "76") (pinfunction "1_76") (pintype "passive"))
    )
    (net (code "65") (name "PA2") (class "Default")
      (node (ref "R20") (pin "2") (pinfunction "2_2") (pintype "passive"))
      (node (ref "U1") (pin "P$35") (pinfunction "PA2_P$35") (pintype "bidirectional"))
      (node (ref "X11") (pin "6") (pinfunction "1_6") (pintype "passive"))
    )
    (net (code "66") (name "PA3") (class "Default")
      (node (ref "R19") (pin "2") (pinfunction "2_2") (pintype "passive"))
      (node (ref "U1") (pin "P$36") (pinfunction "PA3_P$36") (pintype "bidirectional"))
      (node (ref "X11") (pin "8") (pinfunction "1_8") (pintype "passive"))
    )
    (net (code "67") (name "PA4") (class "Default")
      (node (ref "U1") (pin "P$37") (pinfunction "PA4_P$37") (pintype "bidirectional"))
      (node (ref "X11") (pin "10") (pinfunction "1_10") (pintype "passive"))
      (node (ref "X6") (pin "18") (pinfunction "1_18") (pintype "passive"))
    )
    (net (code "68") (name "PA5") (class "Default")
      (node (ref "U1") (pin "P$38") (pinfunction "PA5_P$38") (pintype "bidirectional"))
      (node (ref "X11") (pin "12") (pinfunction "1_12") (pintype "passive"))
      (node (ref "X6") (pin "20") (pinfunction "1_20") (pintype "passive"))
    )
    (net (code "69") (name "PA6") (class "Default")
      (node (ref "U1") (pin "P$40") (pinfunction "PA6_P$40") (pintype "bidirectional"))
      (node (ref "X11") (pin "25") (pinfunction "1_25") (pintype "passive"))
      (node (ref "X8") (pin "16") (pinfunction "1_16") (pintype "passive"))
    )
    (net (code "70") (name "PA7") (class "Default")
      (node (ref "U1") (pin "P$41") (pinfunction "PA7_P$41") (pintype "bidirectional"))
      (node (ref "X11") (pin "27") (pinfunction "1_27") (pintype "passive"))
      (node (ref "X7") (pin "8") (pinfunction "1_8") (pintype "passive"))
    )
    (net (code "71") (name "PB0") (class "Default")
      (node (ref "R18") (pin "1") (pinfunction "1_1") (pintype "passive"))
      (node (ref "U1") (pin "P$95") (pinfunction "PB0_P$95") (pintype "bidirectional"))
      (node (ref "X11") (pin "58") (pinfunction "1_58") (pintype "passive"))
    )
    (net (code "72") (name "PB2") (class "Default")
      (node (ref "U1") (pin "P$91") (pinfunction "PB2_P$91") (pintype "bidirectional"))
      (node (ref "X11") (pin "67") (pinfunction "1_67") (pintype "passive"))
      (node (ref "X8") (pin "17") (pinfunction "1_17") (pintype "passive"))
    )
    (net (code "73") (name "PB3") (class "Default")
      (node (ref "U1") (pin "P$92") (pinfunction "PB3_P$92") (pintype "bidirectional"))
      (node (ref "X11") (pin "69") (pinfunction "1_69") (pintype "passive"))
      (node (ref "X8") (pin "19") (pinfunction "1_19") (pintype "passive"))
    )
    (net (code "74") (name "PB4") (class "Default")
      (node (ref "U1") (pin "P$121") (pinfunction "PB4_P$121") (pintype "bidirectional"))
      (node (ref "X11") (pin "5") (pinfunction "1_5") (pintype "passive"))
      (node (ref "X6") (pin "6") (pinfunction "1_6") (pintype "passive"))
    )
    (net (code "75") (name "PB5") (class "Default")
      (node (ref "U1") (pin "P$120") (pinfunction "PB5_P$120") (pintype "bidirectional"))
      (node (ref "X11") (pin "7") (pinfunction "1_7") (pintype "passive"))
      (node (ref "X6") (pin "8") (pinfunction "1_8") (pintype "passive"))
    )
    (net (code "76") (name "PC4") (class "Default")
      (node (ref "U1") (pin "P$25") (pinfunction "PC4_P$25") (pintype "bidirectional"))
      (node (ref "X11") (pin "23") (pinfunction "1_23") (pintype "passive"))
      (node (ref "X8") (pin "5") (pinfunction "1_5") (pintype "passive"))
    )
    (net (code "77") (name "PC5") (class "Default")
      (node (ref "U1") (pin "P$24") (pinfunction "PC5_P$24") (pintype "bidirectional"))
      (node (ref "X11") (pin "21") (pinfunction "1_21") (pintype "passive"))
      (node (ref "X8") (pin "7") (pinfunction "1_7") (pintype "passive"))
    )
    (net (code "78") (name "PC6") (class "Default")
      (node (ref "U1") (pin "P$23") (pinfunction "PC6_P$23") (pintype "bidirectional"))
      (node (ref "X11") (pin "19") (pinfunction "1_19") (pintype "passive"))
      (node (ref "X8") (pin "9") (pinfunction "1_9") (pintype "passive"))
    )
    (net (code "79") (name "PC7") (class "Default")
      (node (ref "U1") (pin "P$22") (pinfunction "PC7_P$22") (pintype "bidirectional"))
      (node (ref "X11") (pin "17") (pinfunction "1_17") (pintype "passive"))
      (node (ref "X8") (pin "15") (pinfunction "1_15") (pintype "passive"))
    )
    (net (code "80") (name "PD0") (class "Default")
      (node (ref "U1") (pin "P$1") (pinfunction "PD0_P$1") (pintype "bidirectional"))
      (node (ref "X11") (pin "50") (pinfunction "1_50") (pintype "passive"))
      (node (ref "X9") (pin "14") (pinfunction "1_14") (pintype "passive"))
    )
    (net (code "81") (name "PD1") (class "Default")
      (node (ref "U1") (pin "P$2") (pinfunction "PD1_P$2") (pintype "bidirectional"))
      (node (ref "X11") (pin "48") (pinfunction "1_48") (pintype "passive"))
      (node (ref "X9") (pin "12") (pinfunction "1_12") (pintype "passive"))
    )
    (net (code "82") (name "PD2") (class "Default")
      (node (ref "U1") (pin "P$3") (pinfunction "PD2_P$3") (pintype "bidirectional"))
      (node (ref "X11") (pin "52") (pinfunction "1_52") (pintype "passive"))
      (node (ref "X6") (pin "3") (pinfunction "1_3") (pintype "passive"))
    )
    (net (code "83") (name "PD3") (class "Default")
      (node (ref "U1") (pin "P$4") (pinfunction "PD3_P$4") (pintype "bidirectional"))
      (node (ref "X11") (pin "46") (pinfunction "1_46") (pintype "passive"))
      (node (ref "X8") (pin "13") (pinfunction "1_13") (pintype "passive"))
    )
    (net (code "84") (name "PD4") (class "Default")
      (node (ref "JP4") (pin "3") (pinfunction "3_3") (pintype "passive"))
      (node (ref "U1") (pin "P$125") (pinfunction "PD4_P$125") (pintype "bidirectional"))
      (node (ref "X11") (pin "40") (pinfunction "1_40") (pintype "passive"))
    )
    (net (code "85") (name "PD5") (class "Default")
      (node (ref "JP5") (pin "3") (pinfunction "3_3") (pintype "passive"))
      (node (ref "U1") (pin "P$126") (pinfunction "PD5_P$126") (pintype "bidirectional"))
      (node (ref "X11") (pin "38") (pinfunction "1_38") (pintype "passive"))
    )
    (net (code "86") (name "PD6") (class "Default")
      (node (ref "U1") (pin "P$127") (pinfunction "PD6_P$127") (pintype "bidirectional"))
      (node (ref "U4") (pin "4") (pinfunction "*EN2_4") (pintype "input"))
      (node (ref "X11") (pin "44") (pinfunction "1_44") (pintype "passive"))
    )
    (net (code "87") (name "PD7") (class "Default")
      (node (ref "U1") (pin "P$128") (pinfunction "PD7_P$128") (pintype "bidirectional"))
      (node (ref "X11") (pin "42") (pinfunction "1_42") (pintype "passive"))
      (node (ref "X8") (pin "14") (pinfunction "1_14") (pintype "passive"))
    )
    (net (code "88") (name "PE0") (class "Default")
      (node (ref "U1") (pin "P$15") (pinfunction "PE0_P$15") (pintype "bidirectional"))
      (node (ref "X11") (pin "14") (pinfunction "1_14") (pintype "passive"))
      (node (ref "X8") (pin "6") (pinfunction "1_6") (pintype "passive"))
    )
    (net (code "89") (name "PE1") (class "Default")
      (node (ref "U1") (pin "P$14") (pinfunction "PE1_P$14") (pintype "bidirectional"))
      (node (ref "X11") (pin "16") (pinfunction "1_16") (pintype "passive"))
      (node (ref "X8") (pin "8") (pinfunction "1_8") (pintype "passive"))
    )
    (net (code "90") (name "PE2") (class "Default")
      (node (ref "U1") (pin "P$13") (pinfunction "PE2_P$13") (pintype "bidirectional"))
      (node (ref "X11") (pin "18") (pinfunction "1_18") (pintype "passive"))
      (node (ref "X8") (pin "10") (pinfunction "1_10") (pintype "passive"))
    )
    (net (code "91") (name "PE3") (class "Default")
      (node (ref "U1") (pin "P$12") (pinfunction "PE3_P$12") (pintype "bidirectional"))
      (node (ref "X11") (pin "20") (pinfunction "1_20") (pintype "passive"))
      (node (ref "X8") (pin "12") (pinfunction "1_12") (pintype "passive"))
    )
    (net (code "92") (name "PE4") (class "Default")
      (node (ref "U1") (pin "P$123") (pinfunction "PE4_P$123") (pintype "bidirectional"))
      (node (ref "X11") (pin "22") (pinfunction "1_22") (pintype "passive"))
      (node (ref "X8") (pin "3") (pinfunction "1_3") (pintype "passive"))
    )
    (net (code "93") (name "PE5") (class "Default")
      (node (ref "U1") (pin "P$124") (pinfunction "PE5_P$124") (pintype "bidirectional"))
      (node (ref "X11") (pin "24") (pinfunction "1_24") (pintype "passive"))
      (node (ref "X8") (pin "11") (pinfunction "1_11") (pintype "passive"))
    )
    (net (code "94") (name "PF0") (class "Default")
      (node (ref "D4") (pin "A") (pinfunction "A_A") (pintype "passive"))
      (node (ref "U1") (pin "P$42") (pinfunction "PF0_P$42") (pintype "bidirectional"))
      (node (ref "X11") (pin "66") (pinfunction "1_66") (pintype "passive"))
    )
    (net (code "95") (name "PF1") (class "Default")
      (node (ref "U1") (pin "P$43") (pinfunction "PF1_P$43") (pintype "bidirectional"))
      (node (ref "X11") (pin "68") (pinfunction "1_68") (pintype "passive"))
      (node (ref "X9") (pin "1") (pinfunction "1_1") (pintype "passive"))
    )
    (net (code "96") (name "PF2") (class "Default")
      (node (ref "U1") (pin "P$44") (pinfunction "PF2_P$44") (pintype "bidirectional"))
      (node (ref "X11") (pin "70") (pinfunction "1_70") (pintype "passive"))
      (node (ref "X9") (pin "3") (pinfunction "1_3") (pintype "passive"))
    )
    (net (code "97") (name "PF3") (class "Default")
      (node (ref "U1") (pin "P$45") (pinfunction "PF3_P$45") (pintype "bidirectional"))
      (node (ref "X11") (pin "72") (pinfunction "1_72") (pintype "passive"))
      (node (ref "X9") (pin "5") (pinfunction "1_5") (pintype "passive"))
    )
    (net (code "98") (name "PF4") (class "Default")
      (node (ref "D3") (pin "A") (pinfunction "A_A") (pintype "passive"))
      (node (ref "U1") (pin "P$46") (pinfunction "PF4_P$46") (pintype "bidirectional"))
      (node (ref "X11") (pin "64") (pinfunction "1_64") (pintype "passive"))
    )
    (net (code "99") (name "PG0") (class "Default")
      (node (ref "U1") (pin "P$49") (pinfunction "PG0_P$49") (pintype "bidirectional"))
      (node (ref "X11") (pin "31") (pinfunction "1_31") (pintype "passive"))
      (node (ref "X9") (pin "7") (pinfunction "1_7") (pintype "passive"))
    )
    (net (code "100") (name "PG1") (class "Default")
      (node (ref "U1") (pin "P$50") (pinfunction "PG1_P$50") (pintype "bidirectional"))
      (node (ref "X11") (pin "29") (pinfunction "1_29") (pintype "passive"))
      (node (ref "X7") (pin "1") (pinfunction "1_1") (pintype "passive"))
    )
    (net (code "101") (name "PH0") (class "Default")
      (node (ref "U1") (pin "P$29") (pinfunction "PH0_P$29") (pintype "bidirectional"))
      (node (ref "X11") (pin "9") (pinfunction "1_9") (pintype "passive"))
      (node (ref "X7") (pin "13") (pinfunction "1_13") (pintype "passive"))
    )
    (net (code "102") (name "PH1") (class "Default")
      (node (ref "U1") (pin "P$30") (pinfunction "PH1_P$30") (pintype "bidirectional"))
      (node (ref "X11") (pin "11") (pinfunction "1_11") (pintype "passive"))
      (node (ref "X7") (pin "15") (pinfunction "1_15") (pintype "passive"))
    )
    (net (code "103") (name "PH2") (class "Default")
      (node (ref "U1") (pin "P$31") (pinfunction "PH2_P$31") (pintype "bidirectional"))
      (node (ref "X11") (pin "13") (pinfunction "1_13") (pintype "passive"))
      (node (ref "X9") (pin "6") (pinfunction "1_6") (pintype "passive"))
    )
    (net (code "104") (name "PH3") (class "Default")
      (node (ref "U1") (pin "P$32") (pinfunction "PH3_P$32") (pintype "bidirectional"))
      (node (ref "X11") (pin "15") (pinfunction "1_15") (pintype "passive"))
      (node (ref "X9") (pin "8") (pinfunction "1_8") (pintype "passive"))
    )
    (net (code "105") (name "PJ0") (class "Default")
      (node (ref "U1") (pin "P$116") (pinfunction "PJ0_P$116") (pintype "bidirectional"))
      (node (ref "USR_SW1") (pin "P$1") (pinfunction "0_P$1") (pintype "passive"))
      (node (ref "USR_SW1") (pin "P$2") (pinfunction "0_P$2") (pintype "passive"))
      (node (ref "X11") (pin "82") (pinfunction "1_82") (pintype "passive"))
    )
    (net (code "106") (name "PJ1") (class "Default")
      (node (ref "U1") (pin "P$117") (pinfunction "PJ1_P$117") (pintype "bidirectional"))
      (node (ref "USR_SW2") (pin "P$1") (pinfunction "0_P$1") (pintype "passive"))
      (node (ref "USR_SW2") (pin "P$2") (pinfunction "0_P$2") (pintype "passive"))
      (node (ref "X11") (pin "84") (pinfunction "1_84") (pintype "passive"))
    )
    (net (code "107") (name "PK0") (class "Default")
      (node (ref "U1") (pin "P$18") (pinfunction "PK0_P$18") (pintype "bidirectional"))
      (node (ref "X11") (pin "26") (pinfunction "1_26") (pintype "passive"))
      (node (ref "X6") (pin "10") (pinfunction "1_10") (pintype "passive"))
    )
    (net (code "108") (name "PK1") (class "Default")
      (node (ref "U1") (pin "P$19") (pinfunction "PK1_P$19") (pintype "bidirectional"))
      (node (ref "X11") (pin "28") (pinfunction "1_28") (pintype "passive"))
      (node (ref "X6") (pin "12") (pinfunction "1_12") (pintype "passive"))
    )
    (net (code "109") (name "PK2") (class "Default")
      (node (ref "U1") (pin "P$20") (pinfunction "PK2_P$20") (pintype "bidirectional"))
      (node (ref "X11") (pin "30") (pinfunction "1_30") (pintype "passive"))
      (node (ref "X6") (pin "14") (pinfunction "1_14") (pintype "passive"))
    )
    (net (code "110") (name "PK3") (class "Default")
      (node (ref "U1") (pin "P$21") (pinfunction "PK3_P$21") (pintype "bidirectional"))
      (node (ref "X11") (pin "32") (pinfunction "1_32") (pintype "passive"))
      (node (ref "X6") (pin "16") (pinfunction "1_16") (pintype "passive"))
    )
    (net (code "111") (name "PK4") (class "Default")
      (node (ref "U1") (pin "P$63") (pinfunction "PK4_P$63") (pintype "bidirectional"))
      (node (ref "X11") (pin "77") (pinfunction "1_77") (pintype "passive"))
      (node (ref "X7") (pin "3") (pinfunction "1_3") (pintype "passive"))
    )
    (net (code "112") (name "PK5") (class "Default")
      (node (ref "U1") (pin "P$62") (pinfunction "PK5_P$62") (pintype "bidirectional"))
      (node (ref "X11") (pin "75") (pinfunction "1_75") (pintype "passive"))
      (node (ref "X7") (pin "5") (pinfunction "1_5") (pintype "passive"))
    )
    (net (code "113") (name "PK6") (class "Default")
      (node (ref "U1") (pin "P$61") (pinfunction "PK6_P$61") (pintype "bidirectional"))
      (node (ref "X11") (pin "63") (pinfunction "1_63") (pintype "passive"))
      (node (ref "X7") (pin "17") (pinfunction "1_17") (pintype "passive"))
    )
    (net (code "114") (name "PK7") (class "Default")
      (node (ref "U1") (pin "P$60") (pinfunction "PK7_P$60") (pintype "bidirectional"))
      (node (ref "X11") (pin "59") (pinfunction "1_59") (pintype "passive"))
      (node (ref "X7") (pin "19") (pinfunction "1_19") (pintype "passive"))
    )
    (net (code "115") (name "PL0") (class "Default")
      (node (ref "U1") (pin "P$81") (pinfunction "PL0_P$81") (pintype "bidirectional"))
      (node (ref "X11") (pin "43") (pinfunction "1_43") (pintype "passive"))
      (node (ref "X9") (pin "13") (pinfunction "1_13") (pintype "passive"))
    )
    (net (code "116") (name "PL1") (class "Default")
      (node (ref "U1") (pin "P$82") (pinfunction "PL1_P$82") (pintype "bidirectional"))
      (node (ref "X11") (pin "45") (pinfunction "1_45") (pintype "passive"))
      (node (ref "X9") (pin "15") (pinfunction "1_15") (pintype "passive"))
    )
    (net (code "117") (name "PL2") (class "Default")
      (node (ref "U1") (pin "P$83") (pinfunction "PL2_P$83") (pintype "bidirectional"))
      (node (ref "X11") (pin "47") (pinfunction "1_47") (pintype "passive"))
      (node (ref "X9") (pin "17") (pinfunction "1_17") (pintype "passive"))
    )
    (net (code "118") (name "PL3") (class "Default")
      (node (ref "U1") (pin "P$84") (pinfunction "PL3_P$84") (pintype "bidirectional"))
      (node (ref "X11") (pin "49") (pinfunction "1_49") (pintype "passive"))
      (node (ref "X9") (pin "19") (pinfunction "1_19") (pintype "passive"))
    )
    (net (code "119") (name "PL4") (class "Default")
      (node (ref "U1") (pin "P$85") (pinfunction "PL4_P$85") (pintype "bidirectional"))
      (node (ref "X11") (pin "65") (pinfunction "1_65") (pintype "passive"))
      (node (ref "X9") (pin "9") (pinfunction "1_9") (pintype "passive"))
    )
    (net (code "120") (name "PL5") (class "Default")
      (node (ref "U1") (pin "P$86") (pinfunction "PL5_P$86") (pintype "bidirectional"))
      (node (ref "X11") (pin "79") (pinfunction "1_79") (pintype "passive"))
      (node (ref "X9") (pin "11") (pinfunction "1_11") (pintype "passive"))
    )
    (net (code "121") (name "PM0") (class "Default")
      (node (ref "U1") (pin "P$78") (pinfunction "PM0_P$78") (pintype "bidirectional"))
      (node (ref "X11") (pin "41") (pinfunction "1_41") (pintype "passive"))
      (node (ref "X7") (pin "7") (pinfunction "1_7") (pintype "passive"))
    )
    (net (code "122") (name "PM1") (class "Default")
      (node (ref "U1") (pin "P$77") (pinfunction "PM1_P$77") (pintype "bidirectional"))
      (node (ref "X11") (pin "39") (pinfunction "1_39") (pintype "passive"))
      (node (ref "X7") (pin "9") (pinfunction "1_9") (pintype "passive"))
    )
    (net (code "123") (name "PM2") (class "Default")
      (node (ref "U1") (pin "P$76") (pinfunction "PM2_P$76") (pintype "bidirectional"))
      (node (ref "X11") (pin "37") (pinfunction "1_37") (pintype "passive"))
      (node (ref "X7") (pin "11") (pinfunction "1_11") (pintype "passive"))
    )
    (net (code "124") (name "PM3") (class "Default")
      (node (ref "U1") (pin "P$75") (pinfunction "PM3_P$75") (pintype "bidirectional"))
      (node (ref "X11") (pin "33") (pinfunction "1_33") (pintype "passive"))
      (node (ref "X9") (pin "4") (pinfunction "1_4") (pintype "passive"))
    )
    (net (code "125") (name "PM4") (class "Default")
      (node (ref "U1") (pin "P$74") (pinfunction "PM4_P$74") (pintype "bidirectional"))
      (node (ref "X11") (pin "92") (pinfunction "1_92") (pintype "passive"))
      (node (ref "X8") (pin "18") (pinfunction "1_18") (pintype "passive"))
    )
    (net (code "126") (name "PM5") (class "Default")
      (node (ref "U1") (pin "P$73") (pinfunction "PM5_P$73") (pintype "bidirectional"))
      (node (ref "X11") (pin "90") (pinfunction "1_90") (pintype "passive"))
      (node (ref "X8") (pin "20") (pinfunction "1_20") (pintype "passive"))
    )
    (net (code "127") (name "PM6") (class "Default")
      (node (ref "U1") (pin "P$72") (pinfunction "PM6_P$72") (pintype "bidirectional"))
      (node (ref "X11") (pin "88") (pinfunction "1_88") (pintype "passive"))
      (node (ref "X7") (pin "20") (pinfunction "1_20") (pintype "passive"))
    )
    (net (code "128") (name "PM7") (class "Default")
      (node (ref "U1") (pin "P$71") (pinfunction "PM7_P$71") (pintype "bidirectional"))
      (node (ref "X11") (pin "86") (pinfunction "1_86") (pintype "passive"))
      (node (ref "X7") (pin "4") (pinfunction "1_4") (pintype "passive"))
    )
    (net (code "129") (name "PN0") (class "Default")
      (node (ref "D2") (pin "A") (pinfunction "A_A") (pintype "passive"))
      (node (ref "U1") (pin "P$107") (pinfunction "PN0_P$107") (pintype "bidirectional"))
      (node (ref "X11") (pin "85") (pinfunction "1_85") (pintype "passive"))
    )
    (net (code "130") (name "PN1") (class "Default")
      (node (ref "D1") (pin "A") (pinfunction "A_A") (pintype "passive"))
      (node (ref "U1") (pin "P$108") (pinfunction "PN1_P$108") (pintype "bidirectional"))
      (node (ref "X11") (pin "87") (pinfunction "1_87") (pintype "passive"))
    )
    (net (code "131") (name "PN2") (class "Default")
      (node (ref "U1") (pin "P$109") (pinfunction "PN2_P$109") (pintype "bidirectional"))
      (node (ref "X11") (pin "89") (pinfunction "1_89") (pintype "passive"))
      (node (ref "X9") (pin "16") (pinfunction "1_16") (pintype "passive"))
    )
    (net (code "132") (name "PN3") (class "Default")
      (node (ref "U1") (pin "P$110") (pinfunction "PN3_P$110") (pintype "bidirectional"))
      (node (ref "X11") (pin "91") (pinfunction "1_91") (pintype "passive"))
      (node (ref "X9") (pin "18") (pinfunction "1_18") (pintype "passive"))
    )
    (net (code "133") (name "PN4") (class "Default")
      (node (ref "U1") (pin "P$111") (pinfunction "PN4_P$111") (pintype "bidirectional"))
      (node (ref "X11") (pin "81") (pinfunction "1_81") (pintype "passive"))
      (node (ref "X6") (pin "19") (pinfunction "1_19") (pintype "passive"))
    )
    (net (code "134") (name "PN5") (class "Default")
      (node (ref "U1") (pin "P$112") (pinfunction "PN5_P$112") (pintype "bidirectional"))
      (node (ref "X11") (pin "83") (pinfunction "1_83") (pintype "passive"))
      (node (ref "X6") (pin "17") (pinfunction "1_17") (pintype "passive"))
    )
    (net (code "135") (name "PP0") (class "Default")
      (node (ref "U1") (pin "P$118") (pinfunction "PP0_P$118") (pintype "bidirectional"))
      (node (ref "X11") (pin "54") (pinfunction "1_54") (pintype "passive"))
      (node (ref "X6") (pin "5") (pinfunction "1_5") (pintype "passive"))
    )
    (net (code "136") (name "PP1") (class "Default")
      (node (ref "U1") (pin "P$119") (pinfunction "PP1_P$119") (pintype "bidirectional"))
      (node (ref "X11") (pin "56") (pinfunction "1_56") (pintype "passive"))
      (node (ref "X6") (pin "7") (pinfunction "1_7") (pintype "passive"))
    )
    (net (code "137") (name "PP2") (class "Default")
      (node (ref "U1") (pin "P$103") (pinfunction "PP2_P$103") (pintype "bidirectional"))
      (node (ref "X11") (pin "71") (pinfunction "1_71") (pintype "passive"))
      (node (ref "X9") (pin "20") (pinfunction "1_20") (pintype "passive"))
    )
    (net (code "138") (name "PP3") (class "Default")
      (node (ref "U1") (pin "P$104") (pinfunction "PP3_P$104") (pintype "bidirectional"))
      (node (ref "X11") (pin "73") (pinfunction "1_73") (pintype "passive"))
      (node (ref "X7") (pin "16") (pinfunction "1_16") (pintype "passive"))
    )
    (net (code "139") (name "PP4") (class "Default")
      (node (ref "U1") (pin "P$105") (pinfunction "PP4_P$105") (pintype "bidirectional"))
      (node (ref "X11") (pin "78") (pinfunction "1_78") (pintype "passive"))
      (node (ref "X6") (pin "15") (pinfunction "1_15") (pintype "passive"))
    )
    (net (code "140") (name "PP5") (class "Default")
      (node (ref "U1") (pin "P$106") (pinfunction "PP5_P$106") (pintype "bidirectional"))
      (node (ref "X11") (pin "80") (pinfunction "1_80") (pintype "passive"))
      (node (ref "X7") (pin "6") (pinfunction "1_6") (pintype "passive"))
    )
    (net (code "141") (name "PQ0") (class "Default")
      (node (ref "U1") (pin "P$5") (pinfunction "PQ0_P$5") (pintype "bidirectional"))
      (node (ref "X11") (pin "51") (pinfunction "1_51") (pintype "passive"))
      (node (ref "X6") (pin "13") (pinfunction "1_13") (pintype "passive"))
    )
    (net (code "142") (name "PQ1") (class "Default")
      (node (ref "U1") (pin "P$6") (pinfunction "PQ1_P$6") (pintype "bidirectional"))
      (node (ref "X11") (pin "53") (pinfunction "1_53") (pintype "passive"))
      (node (ref "X7") (pin "18") (pinfunction "1_18") (pintype "passive"))
    )
    (net (code "143") (name "PQ2") (class "Default")
      (node (ref "R19") (pin "1") (pinfunction "1_1") (pintype "passive"))
      (node (ref "U1") (pin "P$11") (pinfunction "PQ2_P$11") (pintype "bidirectional"))
      (node (ref "X11") (pin "55") (pinfunction "1_55") (pintype "passive"))
      (node (ref "X7") (pin "12") (pinfunction "1_12") (pintype "passive"))
    )
    (net (code "144") (name "PQ3") (class "Default")
      (node (ref "R20") (pin "1") (pinfunction "1_1") (pintype "passive"))
      (node (ref "U1") (pin "P$27") (pinfunction "PQ3_P$27") (pintype "bidirectional"))
      (node (ref "X11") (pin "57") (pinfunction "1_57") (pintype "passive"))
      (node (ref "X7") (pin "14") (pinfunction "1_14") (pintype "passive"))
    )
    (net (code "145") (name "PQ4") (class "Default")
      (node (ref "U1") (pin "P$102") (pinfunction "PQ4_P$102") (pintype "bidirectional"))
      (node (ref "U4") (pin "5") (pinfunction "*OC2_5") (pintype "output"))
      (node (ref "X11") (pin "93") (pinfunction "1_93") (pintype "passive"))
    )
    (net (code "146") (name "RBIAS") (class "Default")
      (node (ref "R25") (pin "1") (pinfunction "1_1") (pintype "passive"))
      (node (ref "U1") (pin "P$59") (pinfunction "RBIAS_P$59") (pintype "bidirectional"))
    )
    (net (code "147") (name "TARGET_ID") (class "Default")
      (node (ref "R18") (pin "2") (pinfunction "2_2") (pintype "passive"))
      (node (ref "TP7") (pin "TP") (pinfunction "TP_TP") (pintype "input"))
      (node (ref "U2") (pin "2") (pinfunction "D-_2") (pintype "passive"))
      (node (ref "U7") (pin "P4") (pinfunction "ID_P4") (pintype "bidirectional"))
    )
    (net (code "148") (name "TARGET_RXD") (class "Default")
      (node (ref "JP4") (pin "1") (pinfunction "1_1") (pintype "passive"))
      (node (ref "R7") (pin "1") (pinfunction "1_1") (pintype "passive"))
      (node (ref "X1") (pin "12") (pinfunction "1_12") (pintype "passive"))
    )
    (net (code "149") (name "TARGET_TCK{slash}SWCLK") (class "Default")
      (node (ref "R1") (pin "2") (pinfunction "2_2") (pintype "passive"))
      (node (ref "R8") (pin "1") (pinfunction "1_1") (pintype "passive"))
      (node (ref "U1") (pin "P$100") (pinfunction "PC0_P$100") (pintype "bidirectional"))
      (node (ref "X1") (pin "10") (pinfunction "1_10") (pintype "passive"))
    )
    (net (code "150") (name "TARGET_TDI") (class "Default")
      (node (ref "R11") (pin "1") (pinfunction "1_1") (pintype "passive"))
      (node (ref "U1") (pin "P$98") (pinfunction "PC2_P$98") (pintype "bidirectional"))
      (node (ref "X1") (pin "6") (pinfunction "1_6") (pintype "passive"))
    )
    (net (code "151") (name "TARGET_TDO{slash}SWO") (class "Default")
      (node (ref "R15") (pin "1") (pinfunction "1_1") (pintype "passive"))
      (node (ref "U1") (pin "P$97") (pinfunction "PC3_P$97") (pintype "bidirectional"))
      (node (ref "X1") (pin "4") (pinfunction "1_4") (pintype "passive"))
    )
    (net (code "152") (name "TARGET_TMS{slash}SWDIO") (class "Default")
      (node (ref "R10") (pin "1") (pinfunction "1_1") (pintype "passive"))
      (node (ref "R2") (pin "2") (pinfunction "2_2") (pintype "passive"))
      (node (ref "U1") (pin "P$99") (pinfunction "PC1_P$99") (pintype "bidirectional"))
      (node (ref "X1") (pin "8") (pinfunction "1_8") (pintype "passive"))
    )
    (net (code "153") (name "TARGET_TXD") (class "Default")
      (node (ref "JP5") (pin "1") (pinfunction "1_1") (pintype "passive"))
      (node (ref "R6") (pin "1") (pinfunction "1_1") (pintype "passive"))
      (node (ref "X1") (pin "14") (pinfunction "1_14") (pintype "passive"))
    )
    (net (code "154") (name "TARGET_VBUS") (class "Default")
      (node (ref "JP1") (pin "3") (pinfunction "3_3") (pintype "passive"))
      (node (ref "TP4") (pin "TP") (pinfunction "TP_TP") (pintype "input"))
      (node (ref "U1") (pin "P$96") (pinfunction "PB1_P$96") (pintype "bidirectional"))
      (node (ref "U2") (pin "6") (pinfunction "VBUS_6") (pintype "passive"))
      (node (ref "U4") (pin "6") (pinfunction "OUT2_6") (pintype "output"))
      (node (ref "U7") (pin "P1") (pinfunction "VBUS_P1") (pintype "bidirectional"))
      (node (ref "X11") (pin "60") (pinfunction "1_60") (pintype "passive"))
    )
    (net (code "155") (name "USBD_N") (class "Default")
      (node (ref "TP5") (pin "TP") (pinfunction "TP_TP") (pintype "input"))
      (node (ref "U1") (pin "P$93") (pinfunction "PL7_P$93") (pintype "bidirectional"))
      (node (ref "U2") (pin "1") (pinfunction "D+_1") (pintype "passive"))
      (node (ref "U7") (pin "P2") (pinfunction "DM_P2") (pintype "bidirectional"))
    )
    (net (code "156") (name "USBD_P") (class "Default")
      (node (ref "TP6") (pin "TP") (pinfunction "TP_TP") (pintype "input"))
      (node (ref "U1") (pin "P$94") (pinfunction "PL6_P$94") (pintype "bidirectional"))
      (node (ref "U2") (pin "3") (pinfunction "ID_3") (pintype "passive"))
      (node (ref "U7") (pin "P3") (pinfunction "DP_P3") (pintype "bidirectional"))
    )
    (net (code "157") (name "VBUS") (class "Default")
      (node (ref "JP1") (pin "2") (pinfunction "2_2") (pintype "passive"))
      (node (ref "JP1") (pin "4") (pinfunction "4_4") (pintype "passive"))
      (node (ref "JP1") (pin "6") (pinfunction "6_6") (pintype "passive"))
      (node (ref "R35") (pin "1") (pinfunction "1_1") (pintype "passive"))
      (node (ref "R36") (pin "2") (pinfunction "2_2") (pintype "passive"))
      (node (ref "U4") (pin "2") (pinfunction "IN_2") (pintype "input"))
    )
    (net (code "158") (name "VCP_RXD") (class "Default")
      (node (ref "R6") (pin "2") (pinfunction "2_2") (pintype "passive"))
      (node (ref "U20") (pin "P$17") (pinfunction "PA0_P$17") (pintype "bidirectional"))
      (node (ref "X1") (pin "13") (pinfunction "1_13") (pintype "passive"))
    )
    (net (code "159") (name "VCP_TXD") (class "Default")
      (node (ref "R7") (pin "2") (pinfunction "2_2") (pintype "passive"))
      (node (ref "U20") (pin "P$18") (pinfunction "PA1_P$18") (pintype "bidirectional"))
      (node (ref "X1") (pin "11") (pinfunction "1_11") (pintype "passive"))
    )
    (net (code "160") (name "VERSION_0") (class "Default")
      (node (ref "R12") (pin "1") (pinfunction "1_1") (pintype "passive"))
      (node (ref "U20") (pin "P$61") (pinfunction "PD0_P$61") (pintype "bidirectional"))
    )
    (net (code "161") (name "VERSION_1") (class "Default")
      (node (ref "R13") (pin "1") (pinfunction "1_1") (pintype "passive"))
      (node (ref "U20") (pin "P$47") (pinfunction "PB2_P$47") (pintype "bidirectional"))
    )
    (net (code "162") (name "VERSION_2") (class "Default")
      (node (ref "R14") (pin "1") (pinfunction "1_1") (pintype "passive"))
      (node (ref "U20") (pin "P$48") (pinfunction "PB3_P$48") (pintype "bidirectional"))
    )
    (net (code "163") (name "VREF+") (class "Default")
      (node (ref "R41") (pin "1") (pinfunction "1_1") (pintype "passive"))
      (node (ref "TP13") (pin "TP") (pinfunction "TP_TP") (pintype "input"))
      (node (ref "U1") (pin "P$9") (pinfunction "VREFA+_P$9") (pintype "bidirectional"))
      (node (ref "X11") (pin "34") (pinfunction "1_34") (pintype "passive"))
    )
    (net (code "164") (name "unconnected-(JP1-Pad1)") (class "Default")
      (node (ref "JP1") (pin "1") (pinfunction "1_1") (pintype "passive"))
    )
    (net (code "165") (name "unconnected-(U2-N.C.-Pad5)") (class "Default")
      (node (ref "U2") (pin "5") (pinfunction "N.C._5") (pintype "no_connect"))
    )
    (net (code "166") (name "unconnected-(U3-ID-Pad3)") (class "Default")
      (node (ref "U3") (pin "3") (pinfunction "ID_3") (pintype "passive"))
    )
    (net (code "167") (name "unconnected-(U3-N.C.-Pad5)") (class "Default")
      (node (ref "U3") (pin "5") (pinfunction "N.C._5") (pintype "no_connect"))
    )
    (net (code "168") (name "unconnected-(U5-NC-Pad5)") (class "Default")
      (node (ref "U5") (pin "5") (pinfunction "NC_5") (pintype "passive"))
    )
    (net (code "169") (name "unconnected-(U6-P$7-PadP7)") (class "Default")
      (node (ref "U6") (pin "P7") (pinfunction "P$7_P7") (pintype "bidirectional"))
    )
    (net (code "170") (name "unconnected-(U20-PB0-PadP$45)") (class "Default")
      (node (ref "U20") (pin "P$45") (pinfunction "PB0_P$45") (pintype "bidirectional"))
    )
    (net (code "171") (name "unconnected-(U20-PB4-PadP$58)") (class "Default")
      (node (ref "U20") (pin "P$58") (pinfunction "PB4_P$58") (pintype "bidirectional"))
    )
    (net (code "172") (name "unconnected-(U20-PB5-PadP$57)") (class "Default")
      (node (ref "U20") (pin "P$57") (pinfunction "PB5_P$57") (pintype "bidirectional"))
    )
    (net (code "173") (name "unconnected-(U20-PB6-PadP$1)") (class "Default")
      (node (ref "U20") (pin "P$1") (pinfunction "PB6_P$1") (pintype "bidirectional"))
    )
    (net (code "174") (name "unconnected-(U20-PB7-PadP$4)") (class "Default")
      (node (ref "U20") (pin "P$4") (pinfunction "PB7_P$4") (pintype "bidirectional"))
    )
    (net (code "175") (name "unconnected-(U20-PC4-PadP$16)") (class "Default")
      (node (ref "U20") (pin "P$16") (pinfunction "PC4_P$16") (pintype "bidirectional"))
    )
    (net (code "176") (name "unconnected-(U20-PC5-PadP$15)") (class "Default")
      (node (ref "U20") (pin "P$15") (pinfunction "PC5_P$15") (pintype "bidirectional"))
    )
    (net (code "177") (name "unconnected-(U20-PC6-PadP$14)") (class "Default")
      (node (ref "U20") (pin "P$14") (pinfunction "PC6_P$14") (pintype "bidirectional"))
    )
    (net (code "178") (name "unconnected-(U20-PC7-PadP$13)") (class "Default")
      (node (ref "U20") (pin "P$13") (pinfunction "PC7_P$13") (pintype "bidirectional"))
    )
    (net (code "179") (name "unconnected-(U20-PD1-PadP$62)") (class "Default")
      (node (ref "U20") (pin "P$62") (pinfunction "PD1_P$62") (pintype "bidirectional"))
    )
    (net (code "180") (name "unconnected-(U20-PD2-PadP$63)") (class "Default")
      (node (ref "U20") (pin "P$63") (pinfunction "PD2_P$63") (pintype "bidirectional"))
    )
    (net (code "181") (name "unconnected-(U20-PD7-PadP$10)") (class "Default")
      (node (ref "U20") (pin "P$10") (pinfunction "PD7_P$10") (pintype "bidirectional"))
    )
    (net (code "182") (name "unconnected-(U20-PE0-PadP$9)") (class "Default")
      (node (ref "U20") (pin "P$9") (pinfunction "PE0_P$9") (pintype "bidirectional"))
    )
    (net (code "183") (name "unconnected-(U20-PE1-PadP$8)") (class "Default")
      (node (ref "U20") (pin "P$8") (pinfunction "PE1_P$8") (pintype "bidirectional"))
    )
    (net (code "184") (name "unconnected-(U20-PE2-PadP$7)") (class "Default")
      (node (ref "U20") (pin "P$7") (pinfunction "PE2_P$7") (pintype "bidirectional"))
    )
    (net (code "185") (name "unconnected-(U20-PE3-PadP$6)") (class "Default")
      (node (ref "U20") (pin "P$6") (pinfunction "PE3_P$6") (pintype "bidirectional"))
    )
    (net (code "186") (name "unconnected-(U20-PE4-PadP$59)") (class "Default")
      (node (ref "U20") (pin "P$59") (pinfunction "PE4_P$59") (pintype "bidirectional"))
    )
    (net (code "187") (name "unconnected-(U20-PE5-PadP$60)") (class "Default")
      (node (ref "U20") (pin "P$60") (pinfunction "PE5_P$60") (pintype "bidirectional"))
    )
    (net (code "188") (name "unconnected-(U20-PF0-PadP$28)") (class "Default")
      (node (ref "U20") (pin "P$28") (pinfunction "PF0_P$28") (pintype "bidirectional"))
    )
    (net (code "189") (name "unconnected-(U20-PF3-PadP$31)") (class "Default")
      (node (ref "U20") (pin "P$31") (pinfunction "PF3_P$31") (pintype "bidirectional"))
    )
    (net (code "190") (name "unconnected-(U20-PF4-PadP$5)") (class "Default")
      (node (ref "U20") (pin "P$5") (pinfunction "PF4_P$5") (pintype "bidirectional"))
    )
    (net (code "191") (name "unconnected-(U20-XOSC1-PadP$36)") (class "Default")
      (node (ref "U20") (pin "P$36") (pinfunction "XOSC1_P$36") (pintype "bidirectional"))
    )
    (net (code "192") (name "unconnected-(U20-~{HIB}-PadP$33)") (class "Default")
      (node (ref "U20") (pin "P$33") (pinfunction "~{HIB}_P$33") (pintype "bidirectional"))
    )
    (net (code "193") (name "unconnected-(U21-RTCK-Pad7)") (class "Default")
      (node (ref "U21") (pin "7") (pinfunction "RTCK_7") (pintype "bidirectional"))
    )
    (net (code "194") (name "unconnected-(U22A-ID-PadP4)") (class "Default")
      (node (ref "U22") (pin "P4") (pinfunction "ID_P4") (pintype "bidirectional"))
    )
    (net (code "195") (name "unconnected-(Y1-NC2-PadP$2)") (class "Default")
      (node (ref "Y1") (pin "P$2") (pinfunction "NC2_P$2") (pintype "bidirectional"))
    )
    (net (code "196") (name "unconnected-(Y1-NC4-PadP$4)") (class "Default")
      (node (ref "Y1") (pin "P$4") (pinfunction "NC4_P$4") (pintype "bidirectional"))
    )
    (net (code "197") (name "unconnected-(Y2-NC2-PadP$2)") (class "Default")
      (node (ref "Y2") (pin "P$2") (pinfunction "NC2_P$2") (pintype "bidirectional"))
    )
    (net (code "198") (name "unconnected-(Y2-NC4-PadP$4)") (class "Default")
      (node (ref "Y2") (pin "P$4") (pinfunction "NC4_P$4") (pintype "bidirectional"))
    )
    (net (code "199") (name "~{DEBUG_RESET_OUT}") (class "Default")
      (node (ref "R16") (pin "2") (pinfunction "2_2") (pintype "passive"))
      (node (ref "U20") (pin "P$23") (pinfunction "PA6_P$23") (pintype "bidirectional"))
      (node (ref "U6") (pin "P10") (pinfunction "~{RESET}_P10") (pintype "bidirectional"))
      (node (ref "X1") (pin "1") (pinfunction "1_1") (pintype "passive"))
    )
    (net (code "200") (name "~{EXTERNAL_DEBUG}") (class "Default")
      (node (ref "R40") (pin "1") (pinfunction "1_1") (pintype "passive"))
      (node (ref "TP2") (pin "TP") (pinfunction "TP_TP") (pintype "input"))
      (node (ref "U20") (pin "P$24") (pinfunction "PA7_P$24") (pintype "bidirectional"))
    )
    (net (code "201") (name "~{TARGET_RESET}") (class "Default")
      (node (ref "R16") (pin "1") (pinfunction "1_1") (pintype "passive"))
      (node (ref "R51") (pin "1") (pinfunction "1_1") (pintype "passive"))
      (node (ref "RESET") (pin "P$3") (pinfunction "1_P$3") (pintype "passive"))
      (node (ref "RESET") (pin "P$4") (pinfunction "1_P$4") (pintype "passive"))
      (node (ref "X1") (pin "2") (pinfunction "1_2") (pintype "passive"))
      (node (ref "X11") (pin "94") (pinfunction "1_94") (pintype "passive"))
      (node (ref "X7") (pin "10") (pinfunction "1_10") (pintype "passive"))
      (node (ref "X9") (pin "10") (pinfunction "1_10") (pintype "passive"))
    )
    (net (code "202") (name "~{WAKE}") (class "Default")
      (node (ref "R42") (pin "2") (pinfunction "2_2") (pintype "passive"))
      (node (ref "TP10") (pin "TP") (pinfunction "TP_TP") (pintype "input"))
      (node (ref "U1") (pin "P$64") (pinfunction "~{WAKE}_P$64") (pintype "bidirectional"))
      (node (ref "WAKE") (pin "P$1") (pinfunction "0_P$1") (pintype "passive"))
      (node (ref "WAKE") (pin "P$2") (pinfunction "0_P$2") (pintype "passive"))
      (node (ref "X11") (pin "95") (pinfunction "1_95") (pintype "passive"))
    )
  )
)
